# uRinks_v4_0.net
KiCad netlist of a schematic drawn in EAGLE
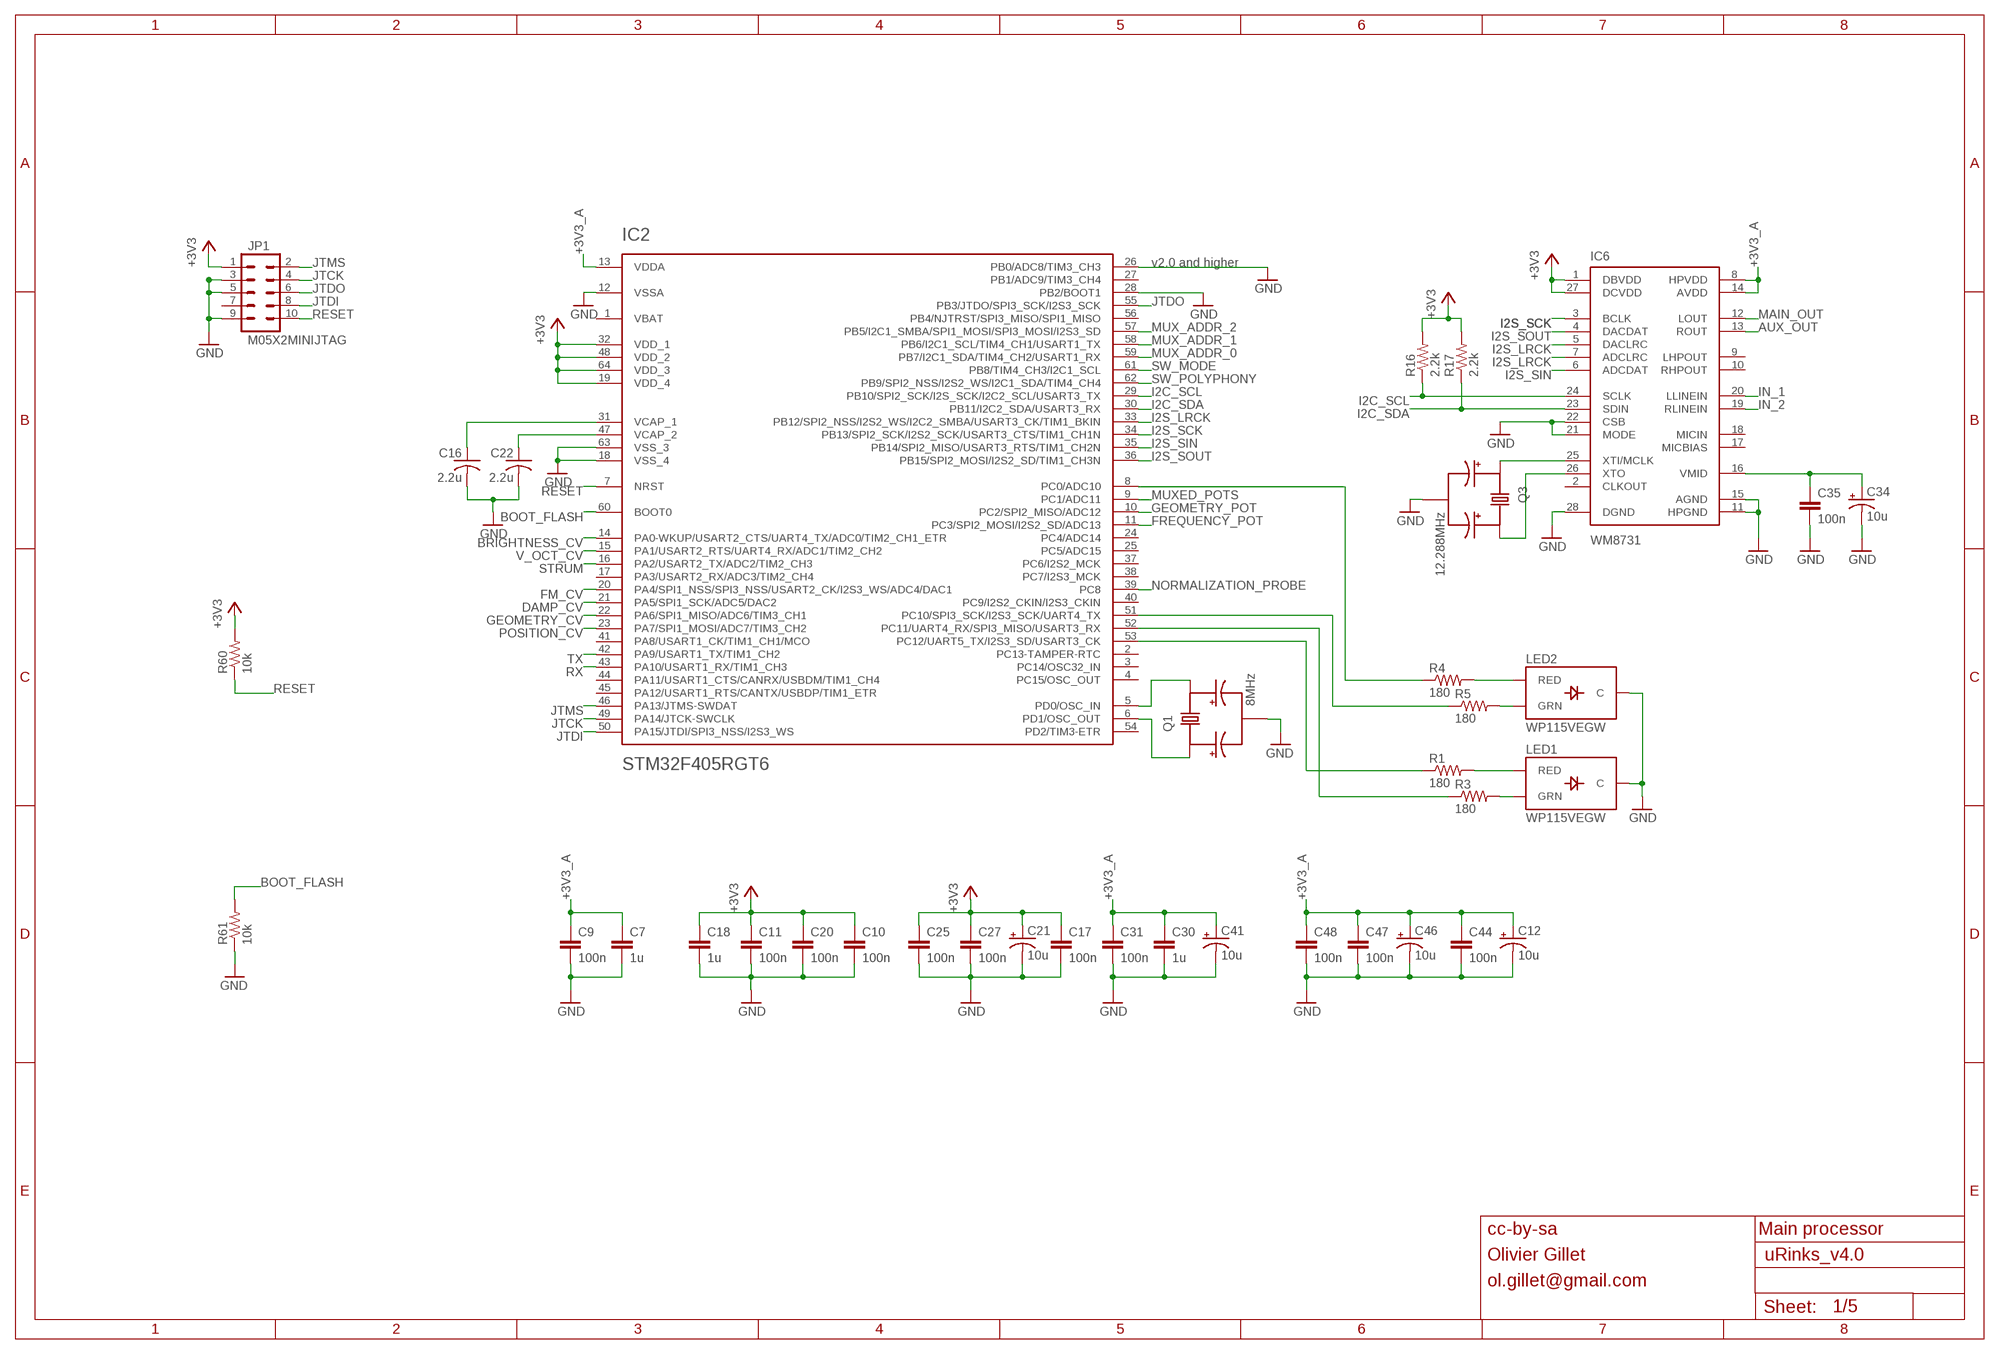
[diagram p0: schematic, sheet 1]
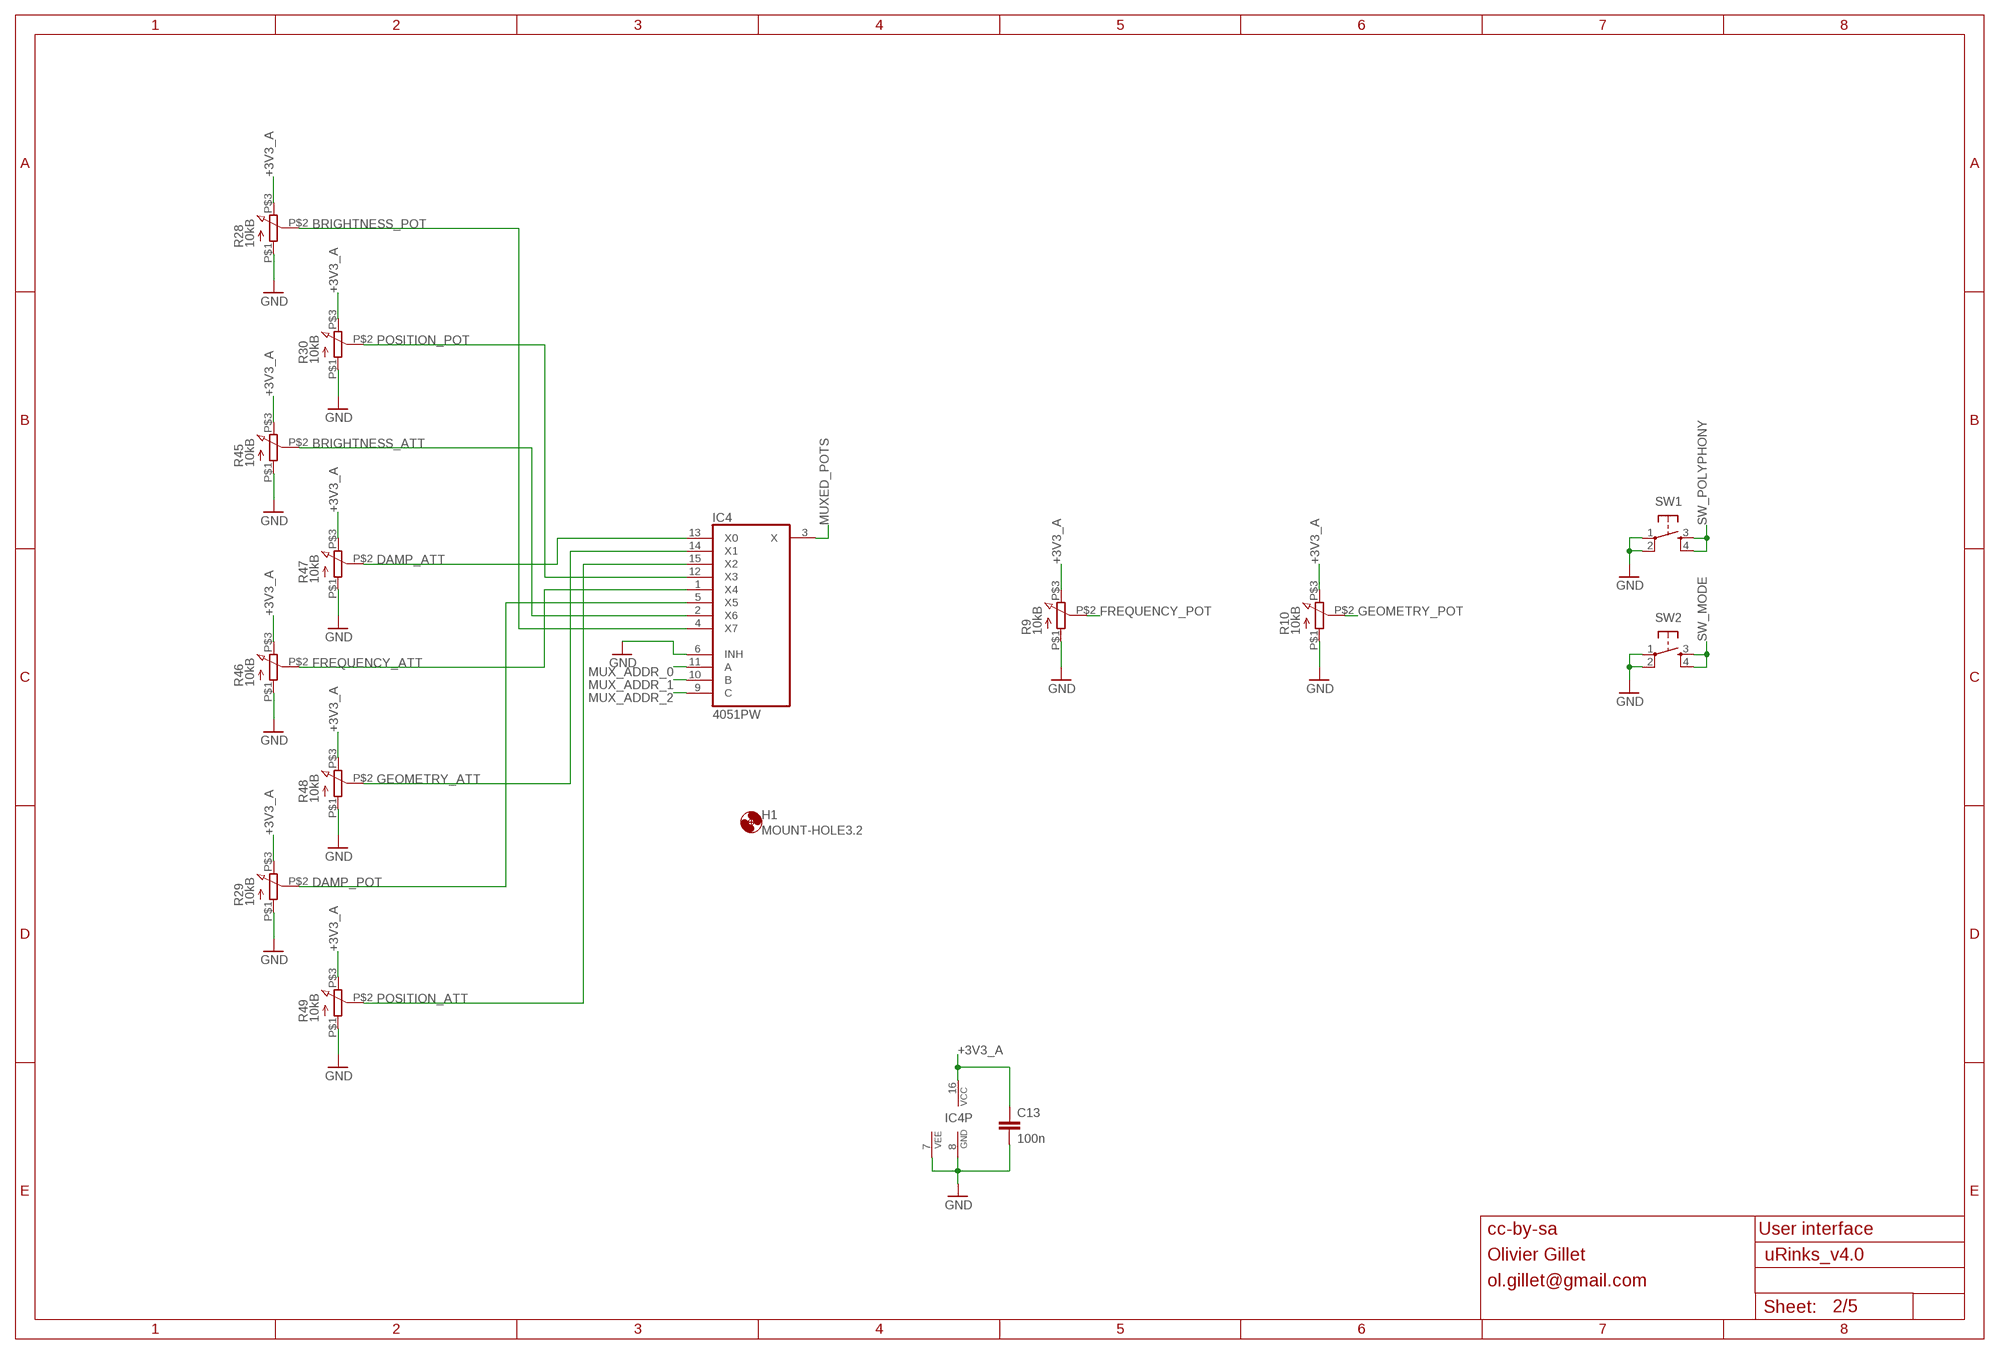
[diagram p1: schematic, sheet 2]
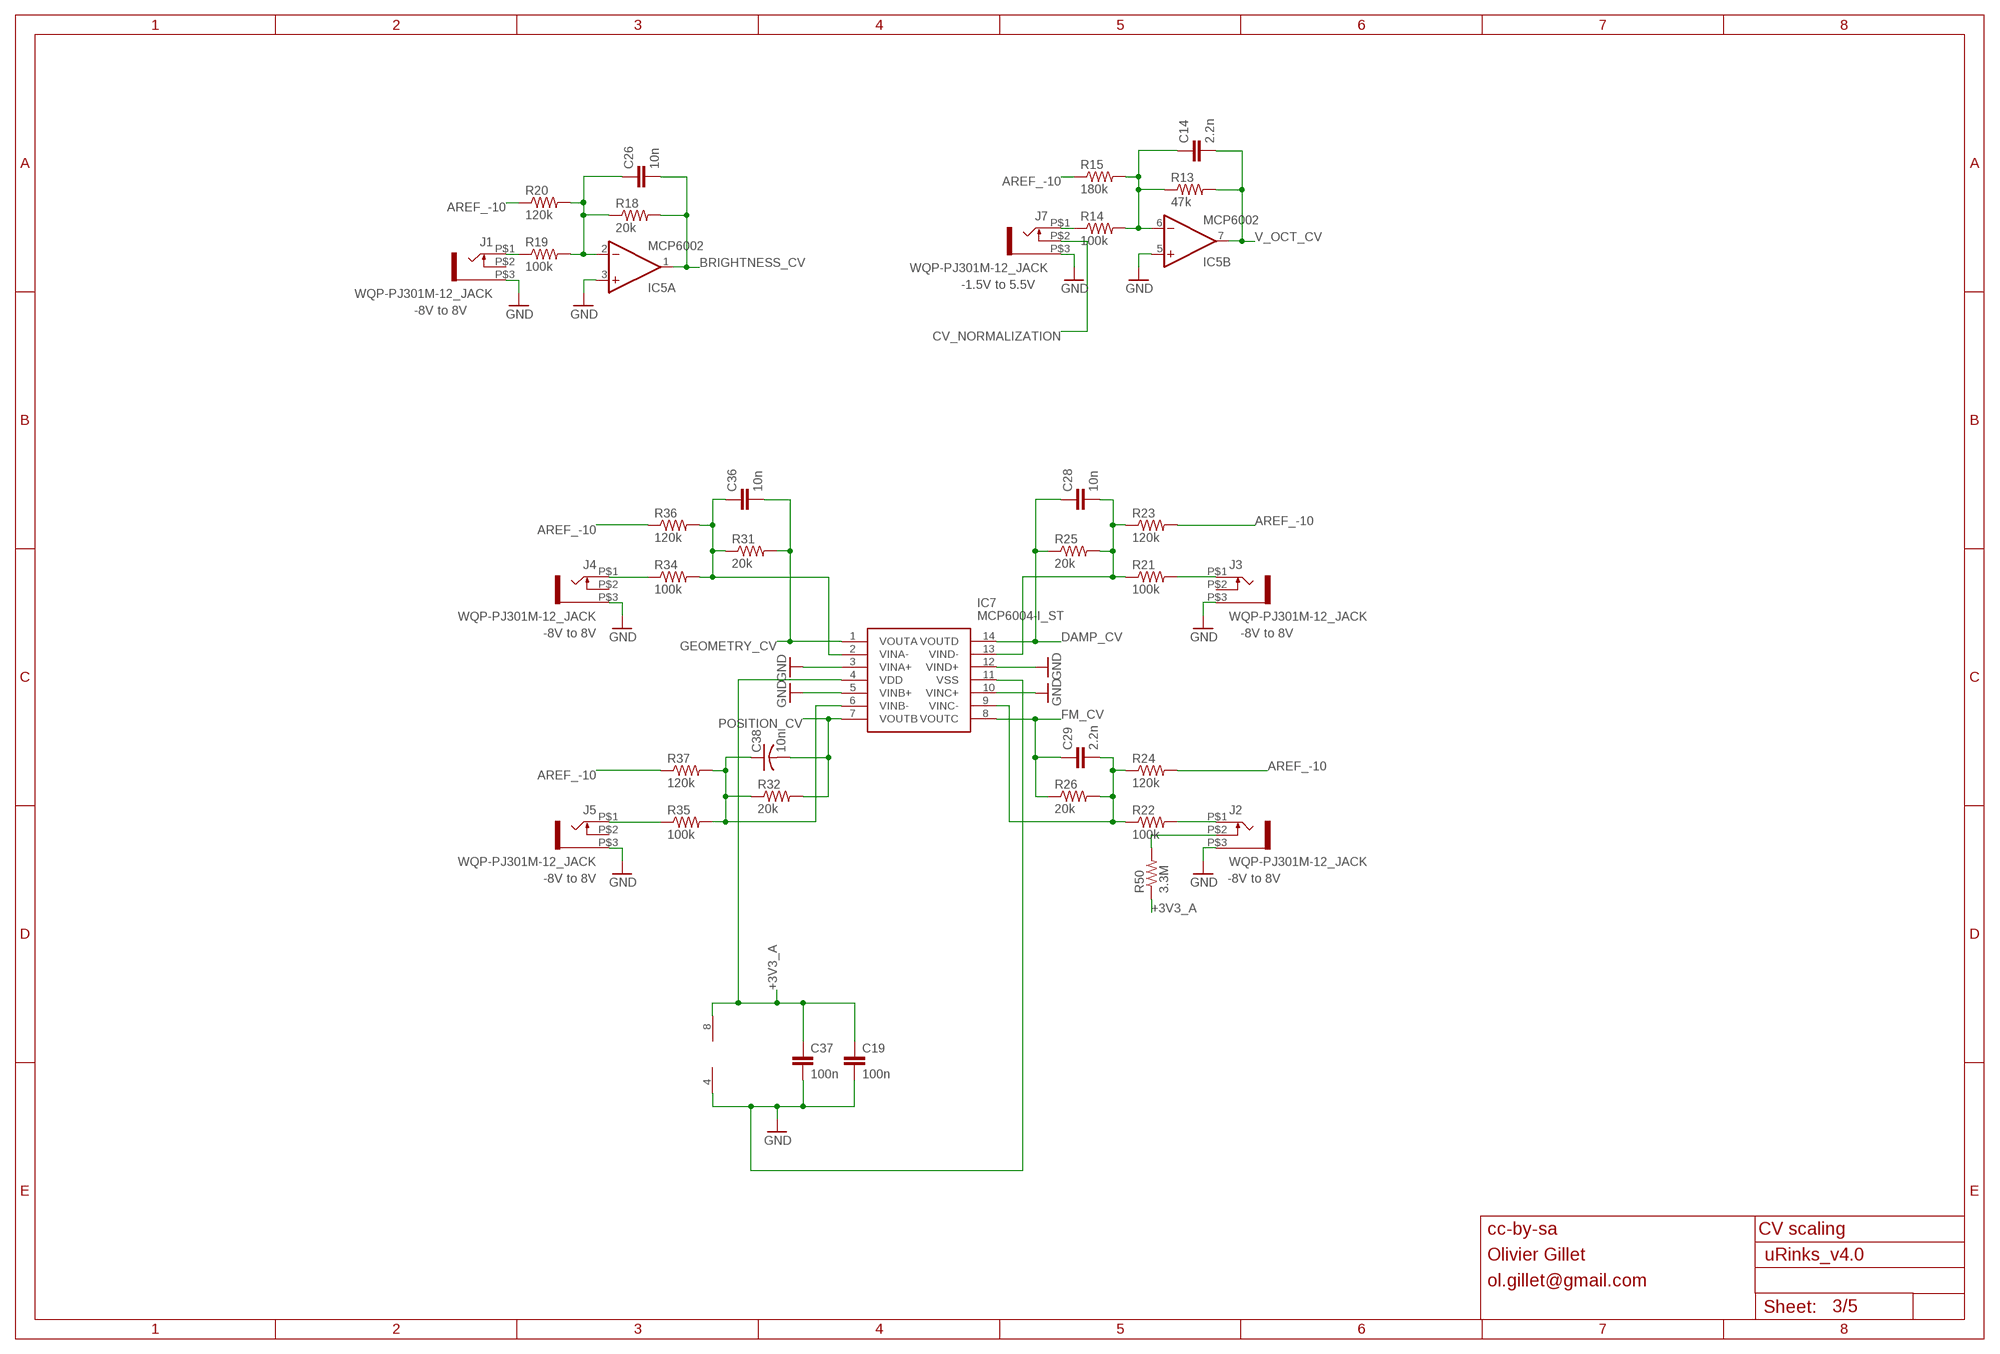
[diagram p2: schematic, sheet 3]
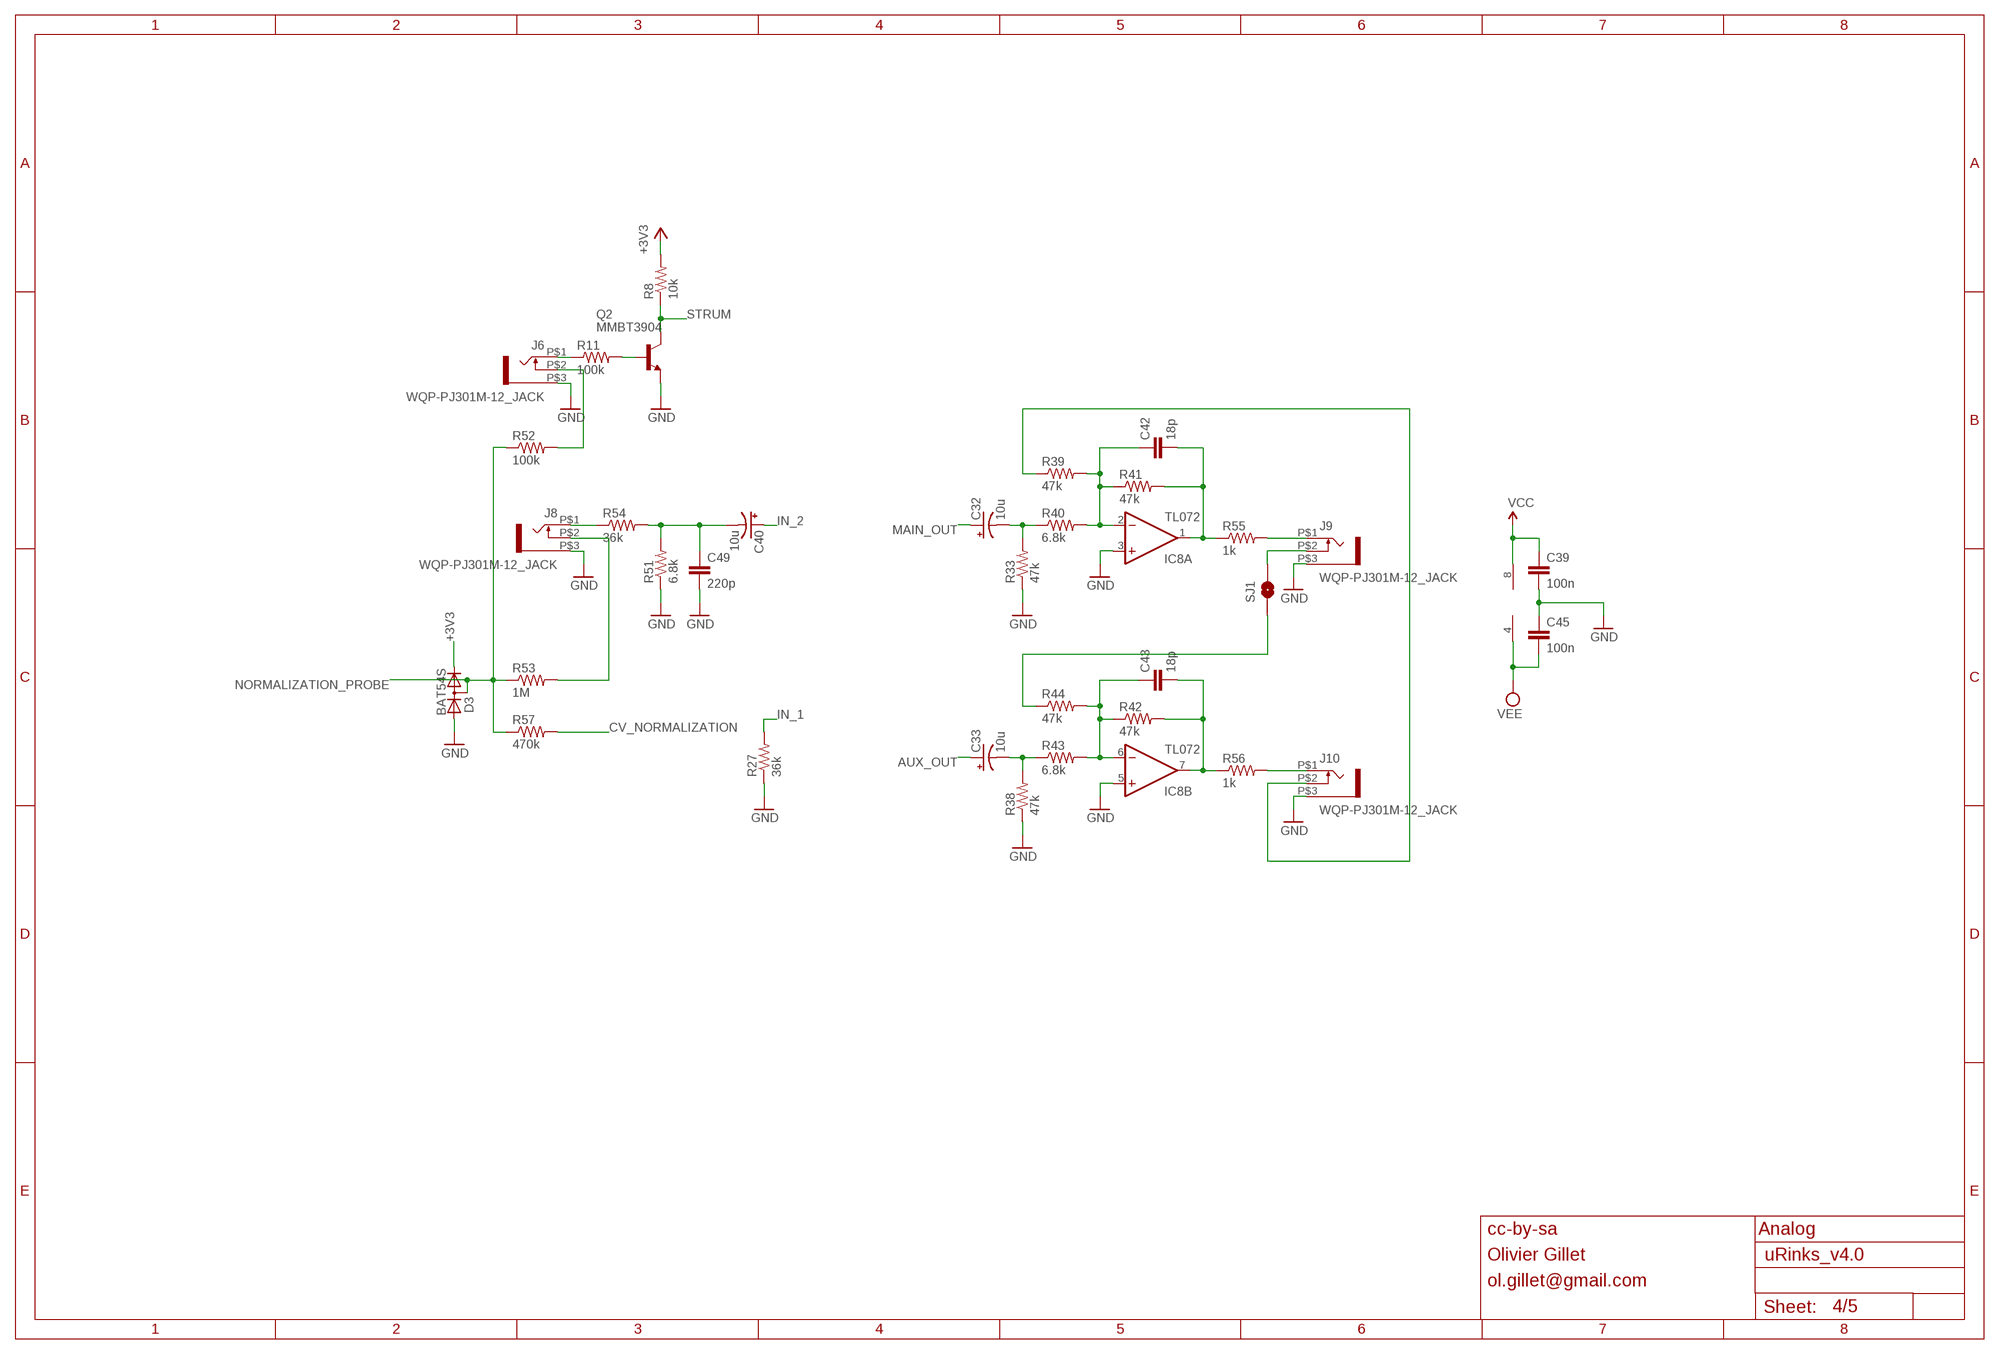
[diagram p3: schematic, sheet 4]
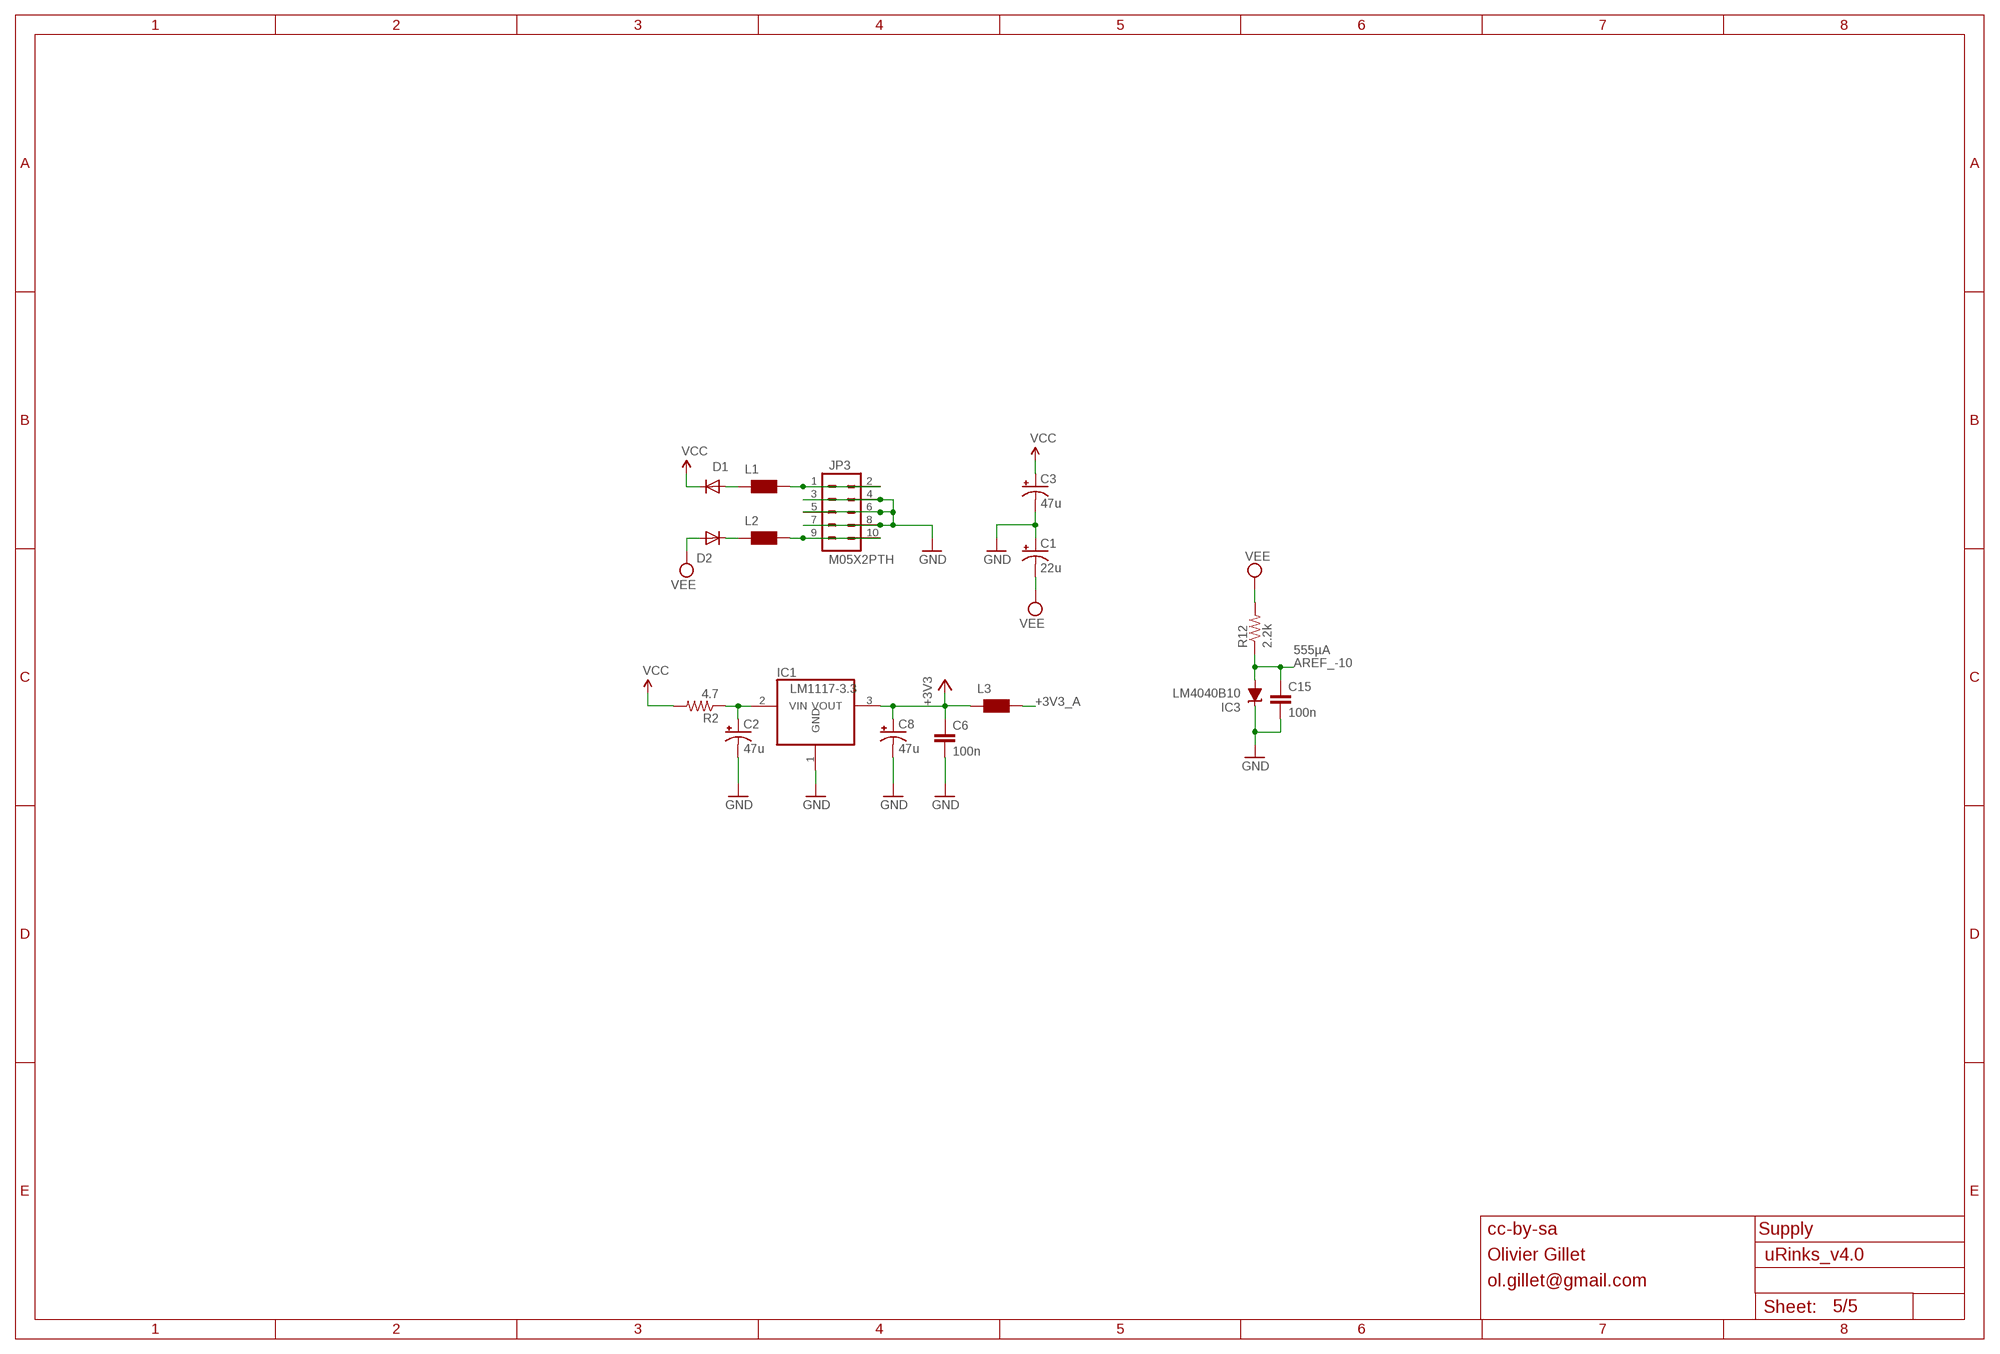
[diagram p4: schematic, sheet 5]

(export (version "E")
  (design (tool "Eeschema 10.0.6"))
  (components
    (comp (ref "C13")
      (value "100n")
      (footprint "eagle-import:PARTS_AMAN_RESISTOR_0603")
      (libsource (lib "eagle-import") (part "PARTS_AMAN_CAPACITOR"))
    )
    (comp (ref "H1")
      (value "MOUNT-HOLE3.2")
      (footprint "eagle-import:3,2")
      (libsource (lib "eagle-import") (part "MOUNT-HOLE3.2"))
    )
    (comp (ref "IC4")
      (value "4051PW")
      (footprint "eagle-import:TSSOP16")
      (libsource (lib "eagle-import") (part "4051PW"))
    )
    (comp (ref "R9")
      (value "10kB")
      (footprint "eagle-import:INSTRUO_Q-POT2")
      (libsource (lib "eagle-import") (part "INSTRUO_Q-POT2"))
    )
    (comp (ref "R10")
      (value "10kB")
      (footprint "eagle-import:INSTRUO_Q-POT2")
      (libsource (lib "eagle-import") (part "INSTRUO_Q-POT2"))
    )
    (comp (ref "R28")
      (value "10kB")
      (footprint "eagle-import:INSTRUO_Q-POT2")
      (libsource (lib "eagle-import") (part "INSTRUO_Q-POT2"))
    )
    (comp (ref "R29")
      (value "10kB")
      (footprint "eagle-import:INSTRUO_Q-POT2")
      (libsource (lib "eagle-import") (part "INSTRUO_Q-POT2"))
    )
    (comp (ref "R30")
      (value "10kB")
      (footprint "eagle-import:INSTRUO_Q-POT2")
      (libsource (lib "eagle-import") (part "INSTRUO_Q-POT2"))
    )
    (comp (ref "R45")
      (value "10kB")
      (footprint "eagle-import:INSTRUO_Q-POT2")
      (libsource (lib "eagle-import") (part "INSTRUO_Q-POT2"))
    )
    (comp (ref "R46")
      (value "10kB")
      (footprint "eagle-import:INSTRUO_Q-POT2")
      (libsource (lib "eagle-import") (part "INSTRUO_Q-POT2"))
    )
    (comp (ref "R47")
      (value "10kB")
      (footprint "eagle-import:INSTRUO_Q-POT2")
      (libsource (lib "eagle-import") (part "INSTRUO_Q-POT2"))
    )
    (comp (ref "R48")
      (value "10kB")
      (footprint "eagle-import:INSTRUO_Q-POT2")
      (libsource (lib "eagle-import") (part "INSTRUO_Q-POT2"))
    )
    (comp (ref "R49")
      (value "10kB")
      (footprint "eagle-import:INSTRUO_Q-POT2")
      (libsource (lib "eagle-import") (part "INSTRUO_Q-POT2"))
    )
    (comp (ref "SW1")
      (value "TAC_SWITCHPTH")
      (footprint "eagle-import:TACTILE-PTH")
      (libsource (lib "eagle-import") (part "TAC_SWITCHPTH"))
    )
    (comp (ref "SW2")
      (value "TAC_SWITCHPTH")
      (footprint "eagle-import:TACTILE-PTH")
      (libsource (lib "eagle-import") (part "TAC_SWITCHPTH"))
    )
    (comp (ref "C1")
      (value "22u")
      (footprint "eagle-import:PANASONIC_C")
      (libsource (lib "eagle-import") (part "CPOL-USC"))
    )
    (comp (ref "C2")
      (value "47u")
      (footprint "eagle-import:PANASONIC_D")
      (libsource (lib "eagle-import") (part "CPOL-USD"))
    )
    (comp (ref "C3")
      (value "47u")
      (footprint "eagle-import:PANASONIC_D")
      (libsource (lib "eagle-import") (part "CPOL-USD"))
    )
    (comp (ref "C6")
      (value "100n")
      (footprint "eagle-import:PARTS_AMAN_RESISTOR_0603")
      (libsource (lib "eagle-import") (part "PARTS_AMAN_CAPACITOR"))
    )
    (comp (ref "C8")
      (value "47u")
      (footprint "eagle-import:PANASONIC_D")
      (libsource (lib "eagle-import") (part "CPOL-USD"))
    )
    (comp (ref "C15")
      (value "100n")
      (footprint "eagle-import:PARTS_AMAN_RESISTOR_0603")
      (libsource (lib "eagle-import") (part "PARTS_AMAN_CAPACITOR"))
    )
    (comp (ref "D1")
      (value "1N5819HW")
      (footprint "eagle-import:SOD123")
      (libsource (lib "eagle-import") (part "DIODE-SOD123"))
    )
    (comp (ref "D2")
      (value "1N5819HW")
      (footprint "eagle-import:SOD123")
      (libsource (lib "eagle-import") (part "DIODE-SOD123"))
    )
    (comp (ref "IC1")
      (value "LM1117-3.3")
      (footprint "eagle-import:TO252")
      (libsource (lib "eagle-import") (part "REG1117T"))
    )
    (comp (ref "IC3")
      (value "LM4040B10")
      (footprint "eagle-import:DBZ_R-PDSO-G3")
      (libsource (lib "eagle-import") (part "LM4041DBZB12"))
    )
    (comp (ref "JP3")
      (value "M05X2PTH")
      (footprint "eagle-import:AVR_ICSP")
      (libsource (lib "eagle-import") (part "M05X2PTH"))
    )
    (comp (ref "L1")
      (value "WE-CBF_0603")
      (footprint "eagle-import:0603")
      (libsource (lib "eagle-import") (part "WE-CBF_0603"))
    )
    (comp (ref "L2")
      (value "WE-CBF_0603")
      (footprint "eagle-import:0603")
      (libsource (lib "eagle-import") (part "WE-CBF_0603"))
    )
    (comp (ref "L3")
      (value "WE-CBF_0603")
      (footprint "eagle-import:0603")
      (libsource (lib "eagle-import") (part "WE-CBF_0603"))
    )
    (comp (ref "R2")
      (value "4.7")
      (footprint "eagle-import:R1206")
      (libsource (lib "eagle-import") (part "R-US_R1206"))
    )
    (comp (ref "R12")
      (value "2.2k")
      (footprint "eagle-import:PARTS_AMAN_RESISTOR_0603")
      (libsource (lib "eagle-import") (part "PARTS_AMAN_RESISTOR"))
    )
    (comp (ref "C14")
      (value "2.2n")
      (footprint "eagle-import:PARTS_AMAN_RESISTOR_0603")
      (libsource (lib "eagle-import") (part "PARTS_AMAN_CAPACITOR"))
    )
    (comp (ref "C19")
      (value "100n")
      (footprint "eagle-import:PARTS_AMAN_RESISTOR_0603")
      (libsource (lib "eagle-import") (part "PARTS_AMAN_CAPACITOR"))
    )
    (comp (ref "C26")
      (value "10n")
      (footprint "eagle-import:PARTS_AMAN_RESISTOR_0603")
      (libsource (lib "eagle-import") (part "PARTS_AMAN_CAPACITOR"))
    )
    (comp (ref "C28")
      (value "10n")
      (footprint "eagle-import:PARTS_AMAN_RESISTOR_0603")
      (libsource (lib "eagle-import") (part "PARTS_AMAN_CAPACITOR"))
    )
    (comp (ref "C29")
      (value "2.2n")
      (footprint "eagle-import:PARTS_AMAN_RESISTOR_0603")
      (libsource (lib "eagle-import") (part "PARTS_AMAN_CAPACITOR"))
    )
    (comp (ref "C36")
      (value "10n")
      (footprint "eagle-import:PARTS_AMAN_RESISTOR_0603")
      (libsource (lib "eagle-import") (part "PARTS_AMAN_CAPACITOR"))
    )
    (comp (ref "C37")
      (value "100n")
      (footprint "eagle-import:PARTS_AMAN_RESISTOR_0603")
      (libsource (lib "eagle-import") (part "PARTS_AMAN_CAPACITOR"))
    )
    (comp (ref "C38")
      (value "10n")
      (footprint "eagle-import:C0603")
      (libsource (lib "eagle-import") (part "resistor_348_C-USC0603"))
    )
    (comp (ref "IC5")
      (value "MCP6002")
      (footprint "eagle-import:SO08")
      (libsource (lib "eagle-import") (part "TL072D"))
    )
    (comp (ref "IC7")
      (value "MCP6004-I_ST")
      (footprint "eagle-import:SOP65P640X120-14N")
      (fields
        (field (name "MANUFACTURER_PART_NUMBER") "MCP6004-I/ST")
        (field (name "MOUSER_PART_NUMBER") "579-MCP6004-I/ST")
      )
      (libsource (lib "eagle-import") (part "MCP6004-I_ST"))
    )
    (comp (ref "J1")
      (value "WQP-PJ301M-12_JACK")
      (footprint "eagle-import:WQP-PJ301M-12_JACK")
      (libsource (lib "eagle-import") (part "WQP-PJ301M-12_JACK"))
    )
    (comp (ref "J2")
      (value "WQP-PJ301M-12_JACK")
      (footprint "eagle-import:WQP-PJ301M-12_JACK")
      (libsource (lib "eagle-import") (part "WQP-PJ301M-12_JACK"))
    )
    (comp (ref "J3")
      (value "WQP-PJ301M-12_JACK")
      (footprint "eagle-import:WQP-PJ301M-12_JACK")
      (libsource (lib "eagle-import") (part "WQP-PJ301M-12_JACK"))
    )
    (comp (ref "J4")
      (value "WQP-PJ301M-12_JACK")
      (footprint "eagle-import:WQP-PJ301M-12_JACK")
      (libsource (lib "eagle-import") (part "WQP-PJ301M-12_JACK"))
    )
    (comp (ref "J5")
      (value "WQP-PJ301M-12_JACK")
      (footprint "eagle-import:WQP-PJ301M-12_JACK")
      (libsource (lib "eagle-import") (part "WQP-PJ301M-12_JACK"))
    )
    (comp (ref "J7")
      (value "WQP-PJ301M-12_JACK")
      (footprint "eagle-import:WQP-PJ301M-12_JACK")
      (libsource (lib "eagle-import") (part "WQP-PJ301M-12_JACK"))
    )
    (comp (ref "R13")
      (value "47k")
      (footprint "eagle-import:PARTS_AMAN_RESISTOR_0603")
      (libsource (lib "eagle-import") (part "PARTS_AMAN_RESISTOR"))
    )
    (comp (ref "R14")
      (value "100k")
      (footprint "eagle-import:PARTS_AMAN_RESISTOR_0603")
      (libsource (lib "eagle-import") (part "PARTS_AMAN_RESISTOR"))
    )
    (comp (ref "R15")
      (value "180k")
      (footprint "eagle-import:PARTS_AMAN_RESISTOR_0603")
      (libsource (lib "eagle-import") (part "PARTS_AMAN_RESISTOR"))
    )
    (comp (ref "R18")
      (value "20k")
      (footprint "eagle-import:PARTS_AMAN_RESISTOR_0603")
      (libsource (lib "eagle-import") (part "PARTS_AMAN_RESISTOR"))
    )
    (comp (ref "R19")
      (value "100k")
      (footprint "eagle-import:PARTS_AMAN_RESISTOR_0603")
      (libsource (lib "eagle-import") (part "PARTS_AMAN_RESISTOR"))
    )
    (comp (ref "R20")
      (value "120k")
      (footprint "eagle-import:PARTS_AMAN_RESISTOR_0603")
      (libsource (lib "eagle-import") (part "PARTS_AMAN_RESISTOR"))
    )
    (comp (ref "R21")
      (value "100k")
      (footprint "eagle-import:PARTS_AMAN_RESISTOR_0603")
      (libsource (lib "eagle-import") (part "PARTS_AMAN_RESISTOR"))
    )
    (comp (ref "R22")
      (value "100k")
      (footprint "eagle-import:PARTS_AMAN_RESISTOR_0603")
      (libsource (lib "eagle-import") (part "PARTS_AMAN_RESISTOR"))
    )
    (comp (ref "R23")
      (value "120k")
      (footprint "eagle-import:PARTS_AMAN_RESISTOR_0603")
      (libsource (lib "eagle-import") (part "PARTS_AMAN_RESISTOR"))
    )
    (comp (ref "R24")
      (value "120k")
      (footprint "eagle-import:PARTS_AMAN_RESISTOR_0603")
      (libsource (lib "eagle-import") (part "PARTS_AMAN_RESISTOR"))
    )
    (comp (ref "R25")
      (value "20k")
      (footprint "eagle-import:PARTS_AMAN_RESISTOR_0603")
      (libsource (lib "eagle-import") (part "PARTS_AMAN_RESISTOR"))
    )
    (comp (ref "R26")
      (value "20k")
      (footprint "eagle-import:PARTS_AMAN_RESISTOR_0603")
      (libsource (lib "eagle-import") (part "PARTS_AMAN_RESISTOR"))
    )
    (comp (ref "R31")
      (value "20k")
      (footprint "eagle-import:PARTS_AMAN_RESISTOR_0603")
      (libsource (lib "eagle-import") (part "PARTS_AMAN_RESISTOR"))
    )
    (comp (ref "R32")
      (value "20k")
      (footprint "eagle-import:PARTS_AMAN_RESISTOR_0603")
      (libsource (lib "eagle-import") (part "PARTS_AMAN_RESISTOR"))
    )
    (comp (ref "R34")
      (value "100k")
      (footprint "eagle-import:PARTS_AMAN_RESISTOR_0603")
      (libsource (lib "eagle-import") (part "PARTS_AMAN_RESISTOR"))
    )
    (comp (ref "R35")
      (value "100k")
      (footprint "eagle-import:PARTS_AMAN_RESISTOR_0603")
      (libsource (lib "eagle-import") (part "PARTS_AMAN_RESISTOR"))
    )
    (comp (ref "R36")
      (value "120k")
      (footprint "eagle-import:PARTS_AMAN_RESISTOR_0603")
      (libsource (lib "eagle-import") (part "PARTS_AMAN_RESISTOR"))
    )
    (comp (ref "R37")
      (value "120k")
      (footprint "eagle-import:PARTS_AMAN_RESISTOR_0603")
      (libsource (lib "eagle-import") (part "PARTS_AMAN_RESISTOR"))
    )
    (comp (ref "R50")
      (value "3.3M")
      (footprint "eagle-import:PARTS_AMAN_RESISTOR_0603")
      (libsource (lib "eagle-import") (part "PARTS_AMAN_RESISTOR"))
    )
    (comp (ref "C32")
      (value "10u")
      (footprint "eagle-import:PANASONIC_A")
      (libsource (lib "eagle-import") (part "CPOL-USA"))
    )
    (comp (ref "C33")
      (value "10u")
      (footprint "eagle-import:PANASONIC_A")
      (libsource (lib "eagle-import") (part "CPOL-USA"))
    )
    (comp (ref "C39")
      (value "100n")
      (footprint "eagle-import:PARTS_AMAN_RESISTOR_0603")
      (libsource (lib "eagle-import") (part "PARTS_AMAN_CAPACITOR"))
    )
    (comp (ref "C40")
      (value "10u")
      (footprint "eagle-import:PANASONIC_A")
      (libsource (lib "eagle-import") (part "CPOL-USA"))
    )
    (comp (ref "C42")
      (value "18p")
      (footprint "eagle-import:PARTS_AMAN_RESISTOR_0603")
      (libsource (lib "eagle-import") (part "PARTS_AMAN_CAPACITOR"))
    )
    (comp (ref "C43")
      (value "18p")
      (footprint "eagle-import:PARTS_AMAN_RESISTOR_0603")
      (libsource (lib "eagle-import") (part "PARTS_AMAN_CAPACITOR"))
    )
    (comp (ref "C45")
      (value "100n")
      (footprint "eagle-import:PARTS_AMAN_RESISTOR_0603")
      (libsource (lib "eagle-import") (part "PARTS_AMAN_CAPACITOR"))
    )
    (comp (ref "C49")
      (value "220p")
      (footprint "eagle-import:PARTS_AMAN_RESISTOR_0603")
      (libsource (lib "eagle-import") (part "PARTS_AMAN_CAPACITOR"))
    )
    (comp (ref "D3")
      (value "BAT54S")
      (footprint "eagle-import:SOT23")
      (libsource (lib "eagle-import") (part "DIODE_2CACA-SOT23"))
    )
    (comp (ref "IC8")
      (value "TL072")
      (footprint "eagle-import:SO08")
      (libsource (lib "eagle-import") (part "og-linear_TL072D"))
    )
    (comp (ref "J6")
      (value "WQP-PJ301M-12_JACK")
      (footprint "eagle-import:WQP-PJ301M-12_JACK")
      (libsource (lib "eagle-import") (part "WQP-PJ301M-12_JACK"))
    )
    (comp (ref "J8")
      (value "WQP-PJ301M-12_JACK")
      (footprint "eagle-import:WQP-PJ301M-12_JACK")
      (libsource (lib "eagle-import") (part "WQP-PJ301M-12_JACK"))
    )
    (comp (ref "J9")
      (value "WQP-PJ301M-12_JACK")
      (footprint "eagle-import:WQP-PJ301M-12_JACK")
      (libsource (lib "eagle-import") (part "WQP-PJ301M-12_JACK"))
    )
    (comp (ref "J10")
      (value "WQP-PJ301M-12_JACK")
      (footprint "eagle-import:WQP-PJ301M-12_JACK")
      (libsource (lib "eagle-import") (part "WQP-PJ301M-12_JACK"))
    )
    (comp (ref "Q2")
      (value "MMBT3904")
      (footprint "eagle-import:SOT23-BEC")
      (libsource (lib "eagle-import") (part "-NPN-SOT23-BECMMBT3904LT1"))
    )
    (comp (ref "R8")
      (value "10k")
      (footprint "eagle-import:PARTS_AMAN_RESISTOR_0603")
      (libsource (lib "eagle-import") (part "PARTS_AMAN_RESISTOR"))
    )
    (comp (ref "R11")
      (value "100k")
      (footprint "eagle-import:PARTS_AMAN_RESISTOR_0603")
      (libsource (lib "eagle-import") (part "PARTS_AMAN_RESISTOR"))
    )
    (comp (ref "R27")
      (value "36k")
      (footprint "eagle-import:PARTS_AMAN_RESISTOR_0603")
      (libsource (lib "eagle-import") (part "PARTS_AMAN_RESISTOR"))
    )
    (comp (ref "R33")
      (value "47k")
      (footprint "eagle-import:PARTS_AMAN_RESISTOR_0603")
      (libsource (lib "eagle-import") (part "PARTS_AMAN_RESISTOR"))
    )
    (comp (ref "R38")
      (value "47k")
      (footprint "eagle-import:PARTS_AMAN_RESISTOR_0603")
      (libsource (lib "eagle-import") (part "PARTS_AMAN_RESISTOR"))
    )
    (comp (ref "R39")
      (value "47k")
      (footprint "eagle-import:PARTS_AMAN_RESISTOR_0603")
      (libsource (lib "eagle-import") (part "PARTS_AMAN_RESISTOR"))
    )
    (comp (ref "R40")
      (value "6.8k")
      (footprint "eagle-import:PARTS_AMAN_RESISTOR_0603")
      (libsource (lib "eagle-import") (part "PARTS_AMAN_RESISTOR"))
    )
    (comp (ref "R41")
      (value "47k")
      (footprint "eagle-import:PARTS_AMAN_RESISTOR_0603")
      (libsource (lib "eagle-import") (part "PARTS_AMAN_RESISTOR"))
    )
    (comp (ref "R42")
      (value "47k")
      (footprint "eagle-import:PARTS_AMAN_RESISTOR_0603")
      (libsource (lib "eagle-import") (part "PARTS_AMAN_RESISTOR"))
    )
    (comp (ref "R43")
      (value "6.8k")
      (footprint "eagle-import:PARTS_AMAN_RESISTOR_0603")
      (libsource (lib "eagle-import") (part "PARTS_AMAN_RESISTOR"))
    )
    (comp (ref "R44")
      (value "47k")
      (footprint "eagle-import:PARTS_AMAN_RESISTOR_0603")
      (libsource (lib "eagle-import") (part "PARTS_AMAN_RESISTOR"))
    )
    (comp (ref "R51")
      (value "6.8k")
      (footprint "eagle-import:PARTS_AMAN_RESISTOR_0603")
      (libsource (lib "eagle-import") (part "PARTS_AMAN_RESISTOR"))
    )
    (comp (ref "R52")
      (value "100k")
      (footprint "eagle-import:R0603")
      (libsource (lib "eagle-import") (part "R-US_R0603"))
    )
    (comp (ref "R53")
      (value "1M")
      (footprint "eagle-import:PARTS_AMAN_RESISTOR_0603")
      (libsource (lib "eagle-import") (part "PARTS_AMAN_RESISTOR"))
    )
    (comp (ref "R54")
      (value "36k")
      (footprint "eagle-import:PARTS_AMAN_RESISTOR_0603")
      (libsource (lib "eagle-import") (part "PARTS_AMAN_RESISTOR"))
    )
    (comp (ref "R55")
      (value "1k")
      (footprint "eagle-import:PARTS_AMAN_RESISTOR_0603")
      (libsource (lib "eagle-import") (part "PARTS_AMAN_RESISTOR"))
    )
    (comp (ref "R56")
      (value "1k")
      (footprint "eagle-import:PARTS_AMAN_RESISTOR_0603")
      (libsource (lib "eagle-import") (part "PARTS_AMAN_RESISTOR"))
    )
    (comp (ref "R57")
      (value "470k")
      (footprint "eagle-import:PARTS_AMAN_RESISTOR_0603")
      (libsource (lib "eagle-import") (part "PARTS_AMAN_RESISTOR"))
    )
    (comp (ref "SJ1")
      (value "SOLDERJUMPERNC2")
      (footprint "eagle-import:SJ_2S-NOTRACE")
      (libsource (lib "eagle-import") (part "SOLDERJUMPERNC2"))
    )
    (comp (ref "C7")
      (value "1u")
      (footprint "eagle-import:PARTS_AMAN_RESISTOR_0603")
      (libsource (lib "eagle-import") (part "PARTS_AMAN_CAPACITOR"))
    )
    (comp (ref "C9")
      (value "100n")
      (footprint "eagle-import:PARTS_AMAN_RESISTOR_0603")
      (libsource (lib "eagle-import") (part "PARTS_AMAN_CAPACITOR"))
    )
    (comp (ref "C10")
      (value "100n")
      (footprint "eagle-import:PARTS_AMAN_RESISTOR_0603")
      (libsource (lib "eagle-import") (part "PARTS_AMAN_CAPACITOR"))
    )
    (comp (ref "C11")
      (value "100n")
      (footprint "eagle-import:PARTS_AMAN_RESISTOR_0603")
      (libsource (lib "eagle-import") (part "PARTS_AMAN_CAPACITOR"))
    )
    (comp (ref "C12")
      (value "10u")
      (footprint "eagle-import:PANASONIC_A")
      (libsource (lib "eagle-import") (part "CPOL-USA"))
    )
    (comp (ref "C16")
      (value "2.2u")
      (footprint "eagle-import:C0805")
      (libsource (lib "eagle-import") (part "C-USC0805"))
    )
    (comp (ref "C17")
      (value "100n")
      (footprint "eagle-import:PARTS_AMAN_RESISTOR_0603")
      (libsource (lib "eagle-import") (part "PARTS_AMAN_CAPACITOR"))
    )
    (comp (ref "C18")
      (value "1u")
      (footprint "eagle-import:PARTS_AMAN_RESISTOR_0603")
      (libsource (lib "eagle-import") (part "PARTS_AMAN_CAPACITOR"))
    )
    (comp (ref "C20")
      (value "100n")
      (footprint "eagle-import:PARTS_AMAN_RESISTOR_0603")
      (libsource (lib "eagle-import") (part "PARTS_AMAN_CAPACITOR"))
    )
    (comp (ref "C21")
      (value "10u")
      (footprint "eagle-import:PANASONIC_A")
      (libsource (lib "eagle-import") (part "CPOL-USA"))
    )
    (comp (ref "C22")
      (value "2.2u")
      (footprint "eagle-import:C0805")
      (libsource (lib "eagle-import") (part "C-USC0805"))
    )
    (comp (ref "C25")
      (value "100n")
      (footprint "eagle-import:PARTS_AMAN_RESISTOR_0603")
      (libsource (lib "eagle-import") (part "PARTS_AMAN_CAPACITOR"))
    )
    (comp (ref "C27")
      (value "100n")
      (footprint "eagle-import:PARTS_AMAN_RESISTOR_0603")
      (libsource (lib "eagle-import") (part "PARTS_AMAN_CAPACITOR"))
    )
    (comp (ref "C30")
      (value "1u")
      (footprint "eagle-import:PARTS_AMAN_RESISTOR_0603")
      (libsource (lib "eagle-import") (part "PARTS_AMAN_CAPACITOR"))
    )
    (comp (ref "C31")
      (value "100n")
      (footprint "eagle-import:PARTS_AMAN_RESISTOR_0603")
      (libsource (lib "eagle-import") (part "PARTS_AMAN_CAPACITOR"))
    )
    (comp (ref "C34")
      (value "10u")
      (footprint "eagle-import:PANASONIC_A")
      (libsource (lib "eagle-import") (part "CPOL-USA"))
    )
    (comp (ref "C35")
      (value "100n")
      (footprint "eagle-import:PARTS_AMAN_RESISTOR_0603")
      (libsource (lib "eagle-import") (part "PARTS_AMAN_CAPACITOR"))
    )
    (comp (ref "C41")
      (value "10u")
      (footprint "eagle-import:PANASONIC_A")
      (libsource (lib "eagle-import") (part "CPOL-USA"))
    )
    (comp (ref "C44")
      (value "100n")
      (footprint "eagle-import:PARTS_AMAN_RESISTOR_0603")
      (libsource (lib "eagle-import") (part "PARTS_AMAN_CAPACITOR"))
    )
    (comp (ref "C46")
      (value "10u")
      (footprint "eagle-import:PANASONIC_A")
      (libsource (lib "eagle-import") (part "CPOL-USA"))
    )
    (comp (ref "C47")
      (value "100n")
      (footprint "eagle-import:PARTS_AMAN_RESISTOR_0603")
      (libsource (lib "eagle-import") (part "PARTS_AMAN_CAPACITOR"))
    )
    (comp (ref "C48")
      (value "100n")
      (footprint "eagle-import:PARTS_AMAN_RESISTOR_0603")
      (libsource (lib "eagle-import") (part "PARTS_AMAN_CAPACITOR"))
    )
    (comp (ref "IC2")
      (value "STM32F405RGT6")
      (footprint "eagle-import:TQFP-10X10-64")
      (libsource (lib "eagle-import") (part "STM32F20X"))
    )
    (comp (ref "IC6")
      (value "WM8731")
      (footprint "eagle-import:SSOP28")
      (libsource (lib "eagle-import") (part "WM8731"))
    )
    (comp (ref "JP1")
      (value "M05X2MINIJTAG")
      (footprint "eagle-import:2X5-1.27")
      (libsource (lib "eagle-import") (part "M05X2MINIJTAG"))
    )
    (comp (ref "LED1")
      (value "WP115VEGW")
      (footprint "eagle-import:LED-BICOLOR-THROUGHHOLE")
      (libsource (lib "eagle-import") (part "LED-BICOLOR-THROUGHHOLE"))
    )
    (comp (ref "LED2")
      (value "WP115VEGW")
      (footprint "eagle-import:LED-BICOLOR-THROUGHHOLE")
      (libsource (lib "eagle-import") (part "LED-BICOLOR-THROUGHHOLE"))
    )
    (comp (ref "Q1")
      (value "8MHz")
      (footprint "eagle-import:INSTRUO_CRYSTAL_SMALLER")
      (libsource (lib "eagle-import") (part "INSTRUO_CRYSTAL_SMALLER"))
    )
    (comp (ref "Q3")
      (value "12.288MHz")
      (footprint "eagle-import:INSTRUO_CRYSTAL_SMALLER")
      (libsource (lib "eagle-import") (part "INSTRUO_CRYSTAL_SMALLER"))
    )
    (comp (ref "R1")
      (value "180")
      (footprint "eagle-import:PARTS_AMAN_RESISTOR_0603")
      (libsource (lib "eagle-import") (part "PARTS_AMAN_RESISTOR"))
    )
    (comp (ref "R3")
      (value "180")
      (footprint "eagle-import:PARTS_AMAN_RESISTOR_0603")
      (libsource (lib "eagle-import") (part "PARTS_AMAN_RESISTOR"))
    )
    (comp (ref "R4")
      (value "180")
      (footprint "eagle-import:PARTS_AMAN_RESISTOR_0603")
      (libsource (lib "eagle-import") (part "PARTS_AMAN_RESISTOR"))
    )
    (comp (ref "R5")
      (value "180")
      (footprint "eagle-import:PARTS_AMAN_RESISTOR_0603")
      (libsource (lib "eagle-import") (part "PARTS_AMAN_RESISTOR"))
    )
    (comp (ref "R16")
      (value "2.2k")
      (footprint "eagle-import:PARTS_AMAN_RESISTOR_0603")
      (libsource (lib "eagle-import") (part "PARTS_AMAN_RESISTOR"))
    )
    (comp (ref "R17")
      (value "2.2k")
      (footprint "eagle-import:PARTS_AMAN_RESISTOR_0603")
      (libsource (lib "eagle-import") (part "PARTS_AMAN_RESISTOR"))
    )
    (comp (ref "R60")
      (value "10k")
      (footprint "eagle-import:PARTS_AMAN_RESISTOR_0603")
      (libsource (lib "eagle-import") (part "PARTS_AMAN_RESISTOR"))
    )
    (comp (ref "R61")
      (value "10k")
      (footprint "eagle-import:PARTS_AMAN_RESISTOR_0603")
      (libsource (lib "eagle-import") (part "PARTS_AMAN_RESISTOR"))
    )
  )
  (nets
    (net (code "1") (name "+3V3") (class "Default")
      (node (ref "C10") (pin "1") (pinfunction "1_1") (pintype "passive"))
      (node (ref "C11") (pin "1") (pinfunction "1_1") (pintype "passive"))
      (node (ref "C17") (pin "1") (pinfunction "1_1") (pintype "passive"))
      (node (ref "C18") (pin "1") (pinfunction "1_1") (pintype "passive"))
      (node (ref "C20") (pin "1") (pinfunction "1_1") (pintype "passive"))
      (node (ref "C21") (pin "+") (pinfunction "+_+") (pintype "passive"))
      (node (ref "C25") (pin "1") (pinfunction "1_1") (pintype "passive"))
      (node (ref "C27") (pin "1") (pinfunction "1_1") (pintype "passive"))
      (node (ref "C6") (pin "1") (pinfunction "1_1") (pintype "passive"))
      (node (ref "C8") (pin "+") (pinfunction "+_+") (pintype "passive"))
      (node (ref "D3") (pin "2") (pinfunction "C_2") (pintype "passive"))
      (node (ref "IC1") (pin "3") (pinfunction "VOUT_3") (pintype "output"))
      (node (ref "IC2") (pin "19") (pinfunction "VDD_4_19") (pintype "power_in"))
      (node (ref "IC2") (pin "32") (pinfunction "VDD_1_32") (pintype "power_in"))
      (node (ref "IC2") (pin "48") (pinfunction "VDD_2_48") (pintype "power_in"))
      (node (ref "IC2") (pin "64") (pinfunction "VDD_3_64") (pintype "power_in"))
      (node (ref "IC6") (pin "1") (pinfunction "DBVDD_1") (pintype "bidirectional"))
      (node (ref "IC6") (pin "27") (pinfunction "DCVDD_27") (pintype "bidirectional"))
      (node (ref "JP1") (pin "1") (pinfunction "1_1") (pintype "passive"))
      (node (ref "L3") (pin "1") (pinfunction "1_1") (pintype "passive"))
      (node (ref "R16") (pin "2") (pinfunction "2_2") (pintype "passive"))
      (node (ref "R17") (pin "2") (pinfunction "2_2") (pintype "passive"))
      (node (ref "R60") (pin "2") (pinfunction "2_2") (pintype "passive"))
      (node (ref "R8") (pin "2") (pinfunction "2_2") (pintype "passive"))
    )
    (net (code "2") (name "+3V3_A") (class "Default")
      (node (ref "C12") (pin "+") (pinfunction "+_+") (pintype "passive"))
      (node (ref "C13") (pin "1") (pinfunction "1_1") (pintype "passive"))
      (node (ref "C19") (pin "1") (pinfunction "1_1") (pintype "passive"))
      (node (ref "C30") (pin "1") (pinfunction "1_1") (pintype "passive"))
      (node (ref "C31") (pin "1") (pinfunction "1_1") (pintype "passive"))
      (node (ref "C37") (pin "1") (pinfunction "1_1") (pintype "passive"))
      (node (ref "C41") (pin "+") (pinfunction "+_+") (pintype "passive"))
      (node (ref "C44") (pin "1") (pinfunction "1_1") (pintype "passive"))
      (node (ref "C46") (pin "+") (pinfunction "+_+") (pintype "passive"))
      (node (ref "C47") (pin "1") (pinfunction "1_1") (pintype "passive"))
      (node (ref "C48") (pin "1") (pinfunction "1_1") (pintype "passive"))
      (node (ref "C7") (pin "1") (pinfunction "1_1") (pintype "passive"))
      (node (ref "C9") (pin "1") (pinfunction "1_1") (pintype "passive"))
      (node (ref "IC2") (pin "13") (pinfunction "VDDA_13") (pintype "power_in"))
      (node (ref "IC4") (pin "16") (pinfunction "VCC_16") (pintype "power_in"))
      (node (ref "IC5") (pin "8") (pinfunction "V+_8") (pintype "power_in"))
      (node (ref "IC6") (pin "14") (pinfunction "AVDD_14") (pintype "bidirectional"))
      (node (ref "IC6") (pin "8") (pinfunction "HPVDD_8") (pintype "bidirectional"))
      (node (ref "IC7") (pin "4") (pinfunction "VDD_4") (pintype "power_in"))
      (node (ref "L3") (pin "2") (pinfunction "2_2") (pintype "passive"))
      (node (ref "R10") (pin "P$3") (pinfunction "3_P$3") (pintype "passive"))
      (node (ref "R28") (pin "P$3") (pinfunction "3_P$3") (pintype "passive"))
      (node (ref "R29") (pin "P$3") (pinfunction "3_P$3") (pintype "passive"))
      (node (ref "R30") (pin "P$3") (pinfunction "3_P$3") (pintype "passive"))
      (node (ref "R45") (pin "P$3") (pinfunction "3_P$3") (pintype "passive"))
      (node (ref "R46") (pin "P$3") (pinfunction "3_P$3") (pintype "passive"))
      (node (ref "R47") (pin "P$3") (pinfunction "3_P$3") (pintype "passive"))
      (node (ref "R48") (pin "P$3") (pinfunction "3_P$3") (pintype "passive"))
      (node (ref "R49") (pin "P$3") (pinfunction "3_P$3") (pintype "passive"))
      (node (ref "R50") (pin "1") (pinfunction "1_1") (pintype "passive"))
      (node (ref "R9") (pin "P$3") (pinfunction "3_P$3") (pintype "passive"))
    )
    (net (code "3") (name "AREF_-10") (class "Default")
      (node (ref "C15") (pin "1") (pinfunction "1_1") (pintype "passive"))
      (node (ref "IC3") (pin "2") (pinfunction "A_2") (pintype "passive"))
      (node (ref "R12") (pin "1") (pinfunction "1_1") (pintype "passive"))
      (node (ref "R15") (pin "1") (pinfunction "1_1") (pintype "passive"))
      (node (ref "R20") (pin "1") (pinfunction "1_1") (pintype "passive"))
      (node (ref "R23") (pin "2") (pinfunction "2_2") (pintype "passive"))
      (node (ref "R24") (pin "2") (pinfunction "2_2") (pintype "passive"))
      (node (ref "R36") (pin "1") (pinfunction "1_1") (pintype "passive"))
      (node (ref "R37") (pin "1") (pinfunction "1_1") (pintype "passive"))
    )
    (net (code "4") (name "AUX_OUT") (class "Default")
      (node (ref "C33") (pin "+") (pinfunction "+_+") (pintype "passive"))
      (node (ref "IC6") (pin "13") (pinfunction "ROUT_13") (pintype "bidirectional"))
    )
    (net (code "5") (name "BOOT_FLASH") (class "Default")
      (node (ref "IC2") (pin "60") (pinfunction "BOOT0_60") (pintype "bidirectional"))
      (node (ref "R61") (pin "2") (pinfunction "2_2") (pintype "passive"))
    )
    (net (code "6") (name "BRIGHTNESS_ATT") (class "Default")
      (node (ref "IC4") (pin "2") (pinfunction "X6_2") (pintype "bidirectional"))
      (node (ref "R45") (pin "P$2") (pinfunction "2_P$2") (pintype "passive"))
    )
    (net (code "7") (name "BRIGHTNESS_CV") (class "Default")
      (node (ref "C26") (pin "2") (pinfunction "2_2") (pintype "passive"))
      (node (ref "IC2") (pin "14") (pinfunction "PA0-WKUP/USART2_CTS/UART4_TX/ADC0/TIM2_CH1_ETR_14") (pintype "bidirectional"))
      (node (ref "IC5") (pin "1") (pinfunction "OUT_1") (pintype "output"))
      (node (ref "R18") (pin "2") (pinfunction "2_2") (pintype "passive"))
    )
    (net (code "8") (name "BRIGHTNESS_POT") (class "Default")
      (node (ref "IC4") (pin "4") (pinfunction "X7_4") (pintype "bidirectional"))
      (node (ref "R28") (pin "P$2") (pinfunction "2_P$2") (pintype "passive"))
    )
    (net (code "9") (name "CV_NORMALIZATION") (class "Default")
      (node (ref "J7") (pin "P$2") (pinfunction "3_P$2") (pintype "passive"))
      (node (ref "R57") (pin "2") (pinfunction "2_2") (pintype "passive"))
    )
    (net (code "10") (name "DAMP_ATT") (class "Default")
      (node (ref "IC4") (pin "13") (pinfunction "X0_13") (pintype "bidirectional"))
      (node (ref "R47") (pin "P$2") (pinfunction "2_P$2") (pintype "passive"))
    )
    (net (code "11") (name "DAMP_CV") (class "Default")
      (node (ref "C28") (pin "1") (pinfunction "1_1") (pintype "passive"))
      (node (ref "IC2") (pin "21") (pinfunction "PA5/SPI1_SCK/ADC5/DAC2_21") (pintype "bidirectional"))
      (node (ref "IC7") (pin "14") (pinfunction "VOUTD_14") (pintype "output"))
      (node (ref "R25") (pin "1") (pinfunction "1_1") (pintype "passive"))
    )
    (net (code "12") (name "DAMP_POT") (class "Default")
      (node (ref "IC4") (pin "5") (pinfunction "X5_5") (pintype "bidirectional"))
      (node (ref "R29") (pin "P$2") (pinfunction "2_P$2") (pintype "passive"))
    )
    (net (code "13") (name "FM_CV") (class "Default")
      (node (ref "C29") (pin "1") (pinfunction "1_1") (pintype "passive"))
      (node (ref "IC2") (pin "20") (pinfunction "PA4/SPI1_NSS/SPI3_NSS/USART2_CK/I2S3_WS/ADC4/DAC1_20") (pintype "bidirectional"))
      (node (ref "IC7") (pin "8") (pinfunction "VOUTC_8") (pintype "output"))
      (node (ref "R26") (pin "1") (pinfunction "1_1") (pintype "passive"))
    )
    (net (code "14") (name "FREQUENCY_ATT") (class "Default")
      (node (ref "IC4") (pin "1") (pinfunction "X4_1") (pintype "bidirectional"))
      (node (ref "R46") (pin "P$2") (pinfunction "2_P$2") (pintype "passive"))
    )
    (net (code "15") (name "FREQUENCY_POT") (class "Default")
      (node (ref "IC2") (pin "11") (pinfunction "PC3/SPI2_MOSI/I2S2_SD/ADC13_11") (pintype "bidirectional"))
      (node (ref "R9") (pin "P$2") (pinfunction "2_P$2") (pintype "passive"))
    )
    (net (code "16") (name "GEOMETRY_ATT") (class "Default")
      (node (ref "IC4") (pin "14") (pinfunction "X1_14") (pintype "bidirectional"))
      (node (ref "R48") (pin "P$2") (pinfunction "2_P$2") (pintype "passive"))
    )
    (net (code "17") (name "GEOMETRY_CV") (class "Default")
      (node (ref "C36") (pin "2") (pinfunction "2_2") (pintype "passive"))
      (node (ref "IC2") (pin "22") (pinfunction "PA6/SPI1_MISO/ADC6/TIM3_CH1_22") (pintype "bidirectional"))
      (node (ref "IC7") (pin "1") (pinfunction "VOUTA_1") (pintype "output"))
      (node (ref "R31") (pin "2") (pinfunction "2_2") (pintype "passive"))
    )
    (net (code "18") (name "GEOMETRY_POT") (class "Default")
      (node (ref "IC2") (pin "10") (pinfunction "PC2/SPI2_MISO/ADC12_10") (pintype "bidirectional"))
      (node (ref "R10") (pin "P$2") (pinfunction "2_P$2") (pintype "passive"))
    )
    (net (code "19") (name "GND") (class "Default")
      (node (ref "C1") (pin "+") (pinfunction "+_+") (pintype "passive"))
      (node (ref "C10") (pin "2") (pinfunction "2_2") (pintype "passive"))
      (node (ref "C11") (pin "2") (pinfunction "2_2") (pintype "passive"))
      (node (ref "C12") (pin "-") (pinfunction "-_-") (pintype "passive"))
      (node (ref "C13") (pin "2") (pinfunction "2_2") (pintype "passive"))
      (node (ref "C15") (pin "2") (pinfunction "2_2") (pintype "passive"))
      (node (ref "C16") (pin "2") (pinfunction "2_2") (pintype "passive"))
      (node (ref "C17") (pin "2") (pinfunction "2_2") (pintype "passive"))
      (node (ref "C18") (pin "2") (pinfunction "2_2") (pintype "passive"))
      (node (ref "C19") (pin "2") (pinfunction "2_2") (pintype "passive"))
      (node (ref "C2") (pin "-") (pinfunction "-_-") (pintype "passive"))
      (node (ref "C20") (pin "2") (pinfunction "2_2") (pintype "passive"))
      (node (ref "C21") (pin "-") (pinfunction "-_-") (pintype "passive"))
      (node (ref "C22") (pin "2") (pinfunction "2_2") (pintype "passive"))
      (node (ref "C25") (pin "2") (pinfunction "2_2") (pintype "passive"))
      (node (ref "C27") (pin "2") (pinfunction "2_2") (pintype "passive"))
      (node (ref "C3") (pin "-") (pinfunction "-_-") (pintype "passive"))
      (node (ref "C30") (pin "2") (pinfunction "2_2") (pintype "passive"))
      (node (ref "C31") (pin "2") (pinfunction "2_2") (pintype "passive"))
      (node (ref "C34") (pin "-") (pinfunction "-_-") (pintype "passive"))
      (node (ref "C35") (pin "2") (pinfunction "2_2") (pintype "passive"))
      (node (ref "C37") (pin "2") (pinfunction "2_2") (pintype "passive"))
      (node (ref "C39") (pin "2") (pinfunction "2_2") (pintype "passive"))
      (node (ref "C41") (pin "-") (pinfunction "-_-") (pintype "passive"))
      (node (ref "C44") (pin "2") (pinfunction "2_2") (pintype "passive"))
      (node (ref "C45") (pin "1") (pinfunction "1_1") (pintype "passive"))
      (node (ref "C46") (pin "-") (pinfunction "-_-") (pintype "passive"))
      (node (ref "C47") (pin "2") (pinfunction "2_2") (pintype "passive"))
      (node (ref "C48") (pin "2") (pinfunction "2_2") (pintype "passive"))
      (node (ref "C49") (pin "2") (pinfunction "2_2") (pintype "passive"))
      (node (ref "C6") (pin "2") (pinfunction "2_2") (pintype "passive"))
      (node (ref "C7") (pin "2") (pinfunction "2_2") (pintype "passive"))
      (node (ref "C8") (pin "-") (pinfunction "-_-") (pintype "passive"))
      (node (ref "C9") (pin "2") (pinfunction "2_2") (pintype "passive"))
      (node (ref "D3") (pin "1") (pinfunction "A_1") (pintype "passive"))
      (node (ref "IC1") (pin "1") (pinfunction "GND_1") (pintype "power_in"))
      (node (ref "IC2") (pin "12") (pinfunction "VSSA_12") (pintype "power_in"))
      (node (ref "IC2") (pin "18") (pinfunction "VSS_4_18") (pintype "power_in"))
      (node (ref "IC2") (pin "26") (pinfunction "PB0/ADC8/TIM3_CH3_26") (pintype "bidirectional"))
      (node (ref "IC2") (pin "28") (pinfunction "PB2/BOOT1_28") (pintype "bidirectional"))
      (node (ref "IC2") (pin "63") (pinfunction "VSS_3_63") (pintype "power_in"))
      (node (ref "IC3") (pin "1") (pinfunction "C_1") (pintype "passive"))
      (node (ref "IC4") (pin "6") (pinfunction "INH_6") (pintype "input"))
      (node (ref "IC4") (pin "7") (pinfunction "VEE_7") (pintype "power_in"))
      (node (ref "IC4") (pin "8") (pinfunction "GND_8") (pintype "power_in"))
      (node (ref "IC5") (pin "3") (pinfunction "+IN_3") (pintype "input"))
      (node (ref "IC5") (pin "4") (pinfunction "V-_4") (pintype "power_in"))
      (node (ref "IC5") (pin "5") (pinfunction "+IN_5") (pintype "input"))
      (node (ref "IC6") (pin "11") (pinfunction "HPGND_11") (pintype "bidirectional"))
      (node (ref "IC6") (pin "15") (pinfunction "AGND_15") (pintype "bidirectional"))
      (node (ref "IC6") (pin "21") (pinfunction "MODE_21") (pintype "bidirectional"))
      (node (ref "IC6") (pin "22") (pinfunction "CSB_22") (pintype "bidirectional"))
      (node (ref "IC6") (pin "28") (pinfunction "DGND_28") (pintype "bidirectional"))
      (node (ref "IC7") (pin "10") (pinfunction "VINC+_10") (pintype "input"))
      (node (ref "IC7") (pin "11") (pinfunction "VSS_11") (pintype "power_in"))
      (node (ref "IC7") (pin "12") (pinfunction "VIND+_12") (pintype "input"))
      (node (ref "IC7") (pin "3") (pinfunction "VINA+_3") (pintype "input"))
      (node (ref "IC7") (pin "5") (pinfunction "VINB+_5") (pintype "input"))
      (node (ref "IC8") (pin "3") (pinfunction "+IN_3") (pintype "input"))
      (node (ref "IC8") (pin "5") (pinfunction "+IN_5") (pintype "input"))
      (node (ref "J1") (pin "P$3") (pinfunction "1_P$3") (pintype "passive"))
      (node (ref "J10") (pin "P$3") (pinfunction "1_P$3") (pintype "passive"))
      (node (ref "J2") (pin "P$3") (pinfunction "1_P$3") (pintype "passive"))
      (node (ref "J3") (pin "P$3") (pinfunction "1_P$3") (pintype "passive"))
      (node (ref "J4") (pin "P$3") (pinfunction "1_P$3") (pintype "passive"))
      (node (ref "J5") (pin "P$3") (pinfunction "1_P$3") (pintype "passive"))
      (node (ref "J6") (pin "P$3") (pinfunction "1_P$3") (pintype "passive"))
      (node (ref "J7") (pin "P$3") (pinfunction "1_P$3") (pintype "passive"))
      (node (ref "J8") (pin "P$3") (pinfunction "1_P$3") (pintype "passive"))
      (node (ref "J9") (pin "P$3") (pinfunction "1_P$3") (pintype "passive"))
      (node (ref "JP1") (pin "3") (pinfunction "3_3") (pintype "passive"))
      (node (ref "JP1") (pin "5") (pinfunction "5_5") (pintype "passive"))
      (node (ref "JP1") (pin "9") (pinfunction "9_9") (pintype "passive"))
      (node (ref "JP3") (pin "3") (pinfunction "3_3") (pintype "passive"))
      (node (ref "JP3") (pin "4") (pinfunction "4_4") (pintype "passive"))
      (node (ref "JP3") (pin "5") (pinfunction "5_5") (pintype "passive"))
      (node (ref "JP3") (pin "6") (pinfunction "6_6") (pintype "passive"))
      (node (ref "JP3") (pin "7") (pinfunction "7_7") (pintype "passive"))
      (node (ref "JP3") (pin "8") (pinfunction "8_8") (pintype "passive"))
      (node (ref "LED1") (pin "2") (pinfunction "C_2") (pintype "bidirectional"))
      (node (ref "LED2") (pin "2") (pinfunction "C_2") (pintype "bidirectional"))
      (node (ref "Q1") (pin "GND") (pinfunction "GND_GND") (pintype "bidirectional"))
      (node (ref "Q2") (pin "E") (pinfunction "E_E") (pintype "passive"))
      (node (ref "Q3") (pin "GND") (pinfunction "GND_GND") (pintype "bidirectional"))
      (node (ref "R10") (pin "P$1") (pinfunction "1_P$1") (pintype "passive"))
      (node (ref "R27") (pin "1") (pinfunction "1_1") (pintype "passive"))
      (node (ref "R28") (pin "P$1") (pinfunction "1_P$1") (pintype "passive"))
      (node (ref "R29") (pin "P$1") (pinfunction "1_P$1") (pintype "passive"))
      (node (ref "R30") (pin "P$1") (pinfunction "1_P$1") (pintype "passive"))
      (node (ref "R33") (pin "1") (pinfunction "1_1") (pintype "passive"))
      (node (ref "R38") (pin "1") (pinfunction "1_1") (pintype "passive"))
      (node (ref "R45") (pin "P$1") (pinfunction "1_P$1") (pintype "passive"))
      (node (ref "R46") (pin "P$1") (pinfunction "1_P$1") (pintype "passive"))
      (node (ref "R47") (pin "P$1") (pinfunction "1_P$1") (pintype "passive"))
      (node (ref "R48") (pin "P$1") (pinfunction "1_P$1") (pintype "passive"))
      (node (ref "R49") (pin "P$1") (pinfunction "1_P$1") (pintype "passive"))
      (node (ref "R51") (pin "1") (pinfunction "1_1") (pintype "passive"))
      (node (ref "R61") (pin "1") (pinfunction "1_1") (pintype "passive"))
      (node (ref "R9") (pin "P$1") (pinfunction "1_P$1") (pintype "passive"))
      (node (ref "SW1") (pin "1") (pinfunction "1_1") (pintype "passive"))
      (node (ref "SW1") (pin "2") (pinfunction "2_2") (pintype "passive"))
      (node (ref "SW2") (pin "1") (pinfunction "1_1") (pintype "passive"))
      (node (ref "SW2") (pin "2") (pinfunction "2_2") (pintype "passive"))
    )
    (net (code "20") (name "I2C_SCL") (class "Default")
      (node (ref "IC2") (pin "29") (pinfunction "PB10/SPI2_SCK/I2S_SCK/I2C2_SCL/USART3_TX_29") (pintype "bidirectional"))
      (node (ref "IC6") (pin "24") (pinfunction "SCLK_24") (pintype "bidirectional"))
      (node (ref "R16") (pin "1") (pinfunction "1_1") (pintype "passive"))
    )
    (net (code "21") (name "I2C_SDA") (class "Default")
      (node (ref "IC2") (pin "30") (pinfunction "PB11/I2C2_SDA/USART3_RX_30") (pintype "bidirectional"))
      (node (ref "IC6") (pin "23") (pinfunction "SDIN_23") (pintype "bidirectional"))
      (node (ref "R17") (pin "1") (pinfunction "1_1") (pintype "passive"))
    )
    (net (code "22") (name "I2S_LRCK") (class "Default")
      (node (ref "IC2") (pin "33") (pinfunction "PB12/SPI2_NSS/I2S2_WS/I2C2_SMBA/USART3_CK/TIM1_BKIN_33") (pintype "bidirectional"))
      (node (ref "IC6") (pin "5") (pinfunction "DACLRC_5") (pintype "bidirectional"))
      (node (ref "IC6") (pin "7") (pinfunction "ADCLRC_7") (pintype "bidirectional"))
    )
    (net (code "23") (name "I2S_SCK") (class "Default")
      (node (ref "IC2") (pin "34") (pinfunction "PB13/SPI2_SCK/I2S2_SCK/USART3_CTS/TIM1_CH1N_34") (pintype "bidirectional"))
      (node (ref "IC6") (pin "3") (pinfunction "BCLK_3") (pintype "bidirectional"))
    )
    (net (code "24") (name "I2S_SIN") (class "Default")
      (node (ref "IC2") (pin "35") (pinfunction "PB14/SPI2_MISO/USART3_RTS/TIM1_CH2N_35") (pintype "bidirectional"))
      (node (ref "IC6") (pin "6") (pinfunction "ADCDAT_6") (pintype "bidirectional"))
    )
    (net (code "25") (name "I2S_SOUT") (class "Default")
      (node (ref "IC2") (pin "36") (pinfunction "PB15/SPI2_MOSI/I2S2_SD/TIM1_CH3N_36") (pintype "bidirectional"))
      (node (ref "IC6") (pin "4") (pinfunction "DACDAT_4") (pintype "bidirectional"))
    )
    (net (code "26") (name "IN_1") (class "Default")
      (node (ref "IC6") (pin "20") (pinfunction "LLINEIN_20") (pintype "bidirectional"))
      (node (ref "R27") (pin "2") (pinfunction "2_2") (pintype "passive"))
    )
    (net (code "27") (name "IN_2") (class "Default")
      (node (ref "C40") (pin "+") (pinfunction "+_+") (pintype "passive"))
      (node (ref "IC6") (pin "19") (pinfunction "RLINEIN_19") (pintype "bidirectional"))
    )
    (net (code "28") (name "JTCK") (class "Default")
      (node (ref "IC2") (pin "49") (pinfunction "PA14/JTCK-SWCLK_49") (pintype "bidirectional"))
      (node (ref "JP1") (pin "4") (pinfunction "4_4") (pintype "passive"))
    )
    (net (code "29") (name "JTDI") (class "Default")
      (node (ref "IC2") (pin "50") (pinfunction "PA15/JTDI/SPI3_NSS/I2S3_WS_50") (pintype "bidirectional"))
      (node (ref "JP1") (pin "8") (pinfunction "8_8") (pintype "passive"))
    )
    (net (code "30") (name "JTDO") (class "Default")
      (node (ref "IC2") (pin "55") (pinfunction "PB3/JTDO/SPI3_SCK/I2S3_SCK_55") (pintype "bidirectional"))
      (node (ref "JP1") (pin "6") (pinfunction "6_6") (pintype "passive"))
    )
    (net (code "31") (name "JTMS") (class "Default")
      (node (ref "IC2") (pin "46") (pinfunction "PA13/JTMS-SWDAT_46") (pintype "bidirectional"))
      (node (ref "JP1") (pin "2") (pinfunction "2_2") (pintype "passive"))
    )
    (net (code "32") (name "MAIN_OUT") (class "Default")
      (node (ref "C32") (pin "+") (pinfunction "+_+") (pintype "passive"))
      (node (ref "IC6") (pin "12") (pinfunction "LOUT_12") (pintype "bidirectional"))
    )
    (net (code "33") (name "MUXED_POTS") (class "Default")
      (node (ref "IC2") (pin "9") (pinfunction "PC1/ADC11_9") (pintype "bidirectional"))
      (node (ref "IC4") (pin "3") (pinfunction "X_3") (pintype "bidirectional"))
    )
    (net (code "34") (name "MUX_ADDR_0") (class "Default")
      (node (ref "IC2") (pin "59") (pinfunction "PB7/I2C1_SDA/TIM4_CH2/USART1_RX_59") (pintype "bidirectional"))
      (node (ref "IC4") (pin "11") (pinfunction "A_11") (pintype "input"))
    )
    (net (code "35") (name "MUX_ADDR_1") (class "Default")
      (node (ref "IC2") (pin "58") (pinfunction "PB6/I2C1_SCL/TIM4_CH1/USART1_TX_58") (pintype "bidirectional"))
      (node (ref "IC4") (pin "10") (pinfunction "B_10") (pintype "input"))
    )
    (net (code "36") (name "MUX_ADDR_2") (class "Default")
      (node (ref "IC2") (pin "57") (pinfunction "PB5/I2C1_SMBA/SPI1_MOSI/SPI3_MOSI/I2S3_SD_57") (pintype "bidirectional"))
      (node (ref "IC4") (pin "9") (pinfunction "C_9") (pintype "input"))
    )
    (net (code "37") (name "NORMALIZATION_PROBE") (class "Default")
      (node (ref "D3") (pin "3") (pinfunction "AC_3") (pintype "passive"))
      (node (ref "IC2") (pin "39") (pinfunction "PC8_39") (pintype "bidirectional"))
      (node (ref "R52") (pin "1") (pinfunction "1_1") (pintype "passive"))
      (node (ref "R53") (pin "1") (pinfunction "1_1") (pintype "passive"))
      (node (ref "R57") (pin "1") (pinfunction "1_1") (pintype "passive"))
    )
    (net (code "38") (name "Net-(C32-Pad-)") (class "Default")
      (node (ref "C32") (pin "-") (pinfunction "-_-") (pintype "passive"))
      (node (ref "R33") (pin "2") (pinfunction "2_2") (pintype "passive"))
      (node (ref "R40") (pin "1") (pinfunction "1_1") (pintype "passive"))
    )
    (net (code "39") (name "Net-(C33-Pad-)") (class "Default")
      (node (ref "C33") (pin "-") (pinfunction "-_-") (pintype "passive"))
      (node (ref "R38") (pin "2") (pinfunction "2_2") (pintype "passive"))
      (node (ref "R43") (pin "1") (pinfunction "1_1") (pintype "passive"))
    )
    (net (code "40") (name "Net-(C40-Pad-)") (class "Default")
      (node (ref "C40") (pin "-") (pinfunction "-_-") (pintype "passive"))
      (node (ref "C49") (pin "1") (pinfunction "1_1") (pintype "passive"))
      (node (ref "R51") (pin "2") (pinfunction "2_2") (pintype "passive"))
      (node (ref "R54") (pin "2") (pinfunction "2_2") (pintype "passive"))
    )
    (net (code "41") (name "Net-(D1-PadA)") (class "Default")
      (node (ref "D1") (pin "A") (pinfunction "A_A") (pintype "passive"))
      (node (ref "L1") (pin "1") (pinfunction "1_1") (pintype "passive"))
    )
    (net (code "42") (name "Net-(D2-PadC)") (class "Default")
      (node (ref "D2") (pin "C") (pinfunction "C_C") (pintype "passive"))
      (node (ref "L2") (pin "1") (pinfunction "1_1") (pintype "passive"))
    )
    (net (code "43") (name "Net-(IC1-VIN)") (class "Default")
      (node (ref "C2") (pin "+") (pinfunction "+_+") (pintype "passive"))
      (node (ref "IC1") (pin "2") (pinfunction "VIN_2") (pintype "input"))
      (node (ref "R2") (pin "1") (pinfunction "1_1") (pintype "passive"))
    )
    (net (code "44") (name "Net-(IC2-PC0{slash}ADC10)") (class "Default")
      (node (ref "IC2") (pin "8") (pinfunction "PC0/ADC10_8") (pintype "bidirectional"))
      (node (ref "R4") (pin "1") (pinfunction "1_1") (pintype "passive"))
    )
    (net (code "45") (name "Net-(IC2-PC10{slash}SPI3_SCK{slash}I2S3_SCK{slash}UART4_TX)") (class "Default")
      (node (ref "IC2") (pin "51") (pinfunction "PC10/SPI3_SCK/I2S3_SCK/UART4_TX_51") (pintype "bidirectional"))
      (node (ref "R5") (pin "1") (pinfunction "1_1") (pintype "passive"))
    )
    (net (code "46") (name "Net-(IC2-PC11{slash}UART4_RX{slash}SPI3_MISO{slash}USART3_RX)") (class "Default")
      (node (ref "IC2") (pin "52") (pinfunction "PC11/UART4_RX/SPI3_MISO/USART3_RX_52") (pintype "bidirectional"))
      (node (ref "R3") (pin "1") (pinfunction "1_1") (pintype "passive"))
    )
    (net (code "47") (name "Net-(IC2-PC12{slash}UART5_TX{slash}I2S3_SD{slash}USART3_CK)") (class "Default")
      (node (ref "IC2") (pin "53") (pinfunction "PC12/UART5_TX/I2S3_SD/USART3_CK_53") (pintype "bidirectional"))
      (node (ref "R1") (pin "1") (pinfunction "1_1") (pintype "passive"))
    )
    (net (code "48") (name "Net-(IC2-PD0{slash}OSC_IN)") (class "Default")
      (node (ref "IC2") (pin "5") (pinfunction "PD0/OSC_IN_5") (pintype "bidirectional"))
      (node (ref "Q1") (pin "X2") (pinfunction "X2_X2") (pintype "bidirectional"))
    )
    (net (code "49") (name "Net-(IC2-PD1{slash}OSC_OUT)") (class "Default")
      (node (ref "IC2") (pin "6") (pinfunction "PD1/OSC_OUT_6") (pintype "bidirectional"))
      (node (ref "Q1") (pin "X1") (pinfunction "X1_X1") (pintype "bidirectional"))
    )
    (net (code "50") (name "Net-(IC2-VCAP_1)") (class "Default")
      (node (ref "C16") (pin "1") (pinfunction "1_1") (pintype "passive"))
      (node (ref "IC2") (pin "31") (pinfunction "VCAP_1_31") (pintype "power_in"))
    )
    (net (code "51") (name "Net-(IC2-VCAP_2)") (class "Default")
      (node (ref "C22") (pin "1") (pinfunction "1_1") (pintype "passive"))
      (node (ref "IC2") (pin "47") (pinfunction "VCAP_2_47") (pintype "power_in"))
    )
    (net (code "52") (name "Net-(IC5A--IN)") (class "Default")
      (node (ref "C26") (pin "1") (pinfunction "1_1") (pintype "passive"))
      (node (ref "IC5") (pin "2") (pinfunction "-IN_2") (pintype "input"))
      (node (ref "R18") (pin "1") (pinfunction "1_1") (pintype "passive"))
      (node (ref "R19") (pin "2") (pinfunction "2_2") (pintype "passive"))
      (node (ref "R20") (pin "2") (pinfunction "2_2") (pintype "passive"))
    )
    (net (code "53") (name "Net-(IC5B--IN)") (class "Default")
      (node (ref "C14") (pin "1") (pinfunction "1_1") (pintype "passive"))
      (node (ref "IC5") (pin "6") (pinfunction "-IN_6") (pintype "input"))
      (node (ref "R13") (pin "1") (pinfunction "1_1") (pintype "passive"))
      (node (ref "R14") (pin "2") (pinfunction "2_2") (pintype "passive"))
      (node (ref "R15") (pin "2") (pinfunction "2_2") (pintype "passive"))
    )
    (net (code "54") (name "Net-(IC6-VMID)") (class "Default")
      (node (ref "C34") (pin "+") (pinfunction "+_+") (pintype "passive"))
      (node (ref "C35") (pin "1") (pinfunction "1_1") (pintype "passive"))
      (node (ref "IC6") (pin "16") (pinfunction "VMID_16") (pintype "bidirectional"))
    )
    (net (code "55") (name "Net-(IC6-XTI{slash}MCLK)") (class "Default")
      (node (ref "IC6") (pin "25") (pinfunction "XTI/MCLK_25") (pintype "bidirectional"))
      (node (ref "Q3") (pin "X1") (pinfunction "X1_X1") (pintype "bidirectional"))
    )
    (net (code "56") (name "Net-(IC6-XTO)") (class "Default")
      (node (ref "IC6") (pin "26") (pinfunction "XTO_26") (pintype "bidirectional"))
      (node (ref "Q3") (pin "X2") (pinfunction "X2_X2") (pintype "bidirectional"))
    )
    (net (code "57") (name "Net-(IC7-VINA-)") (class "Default")
      (node (ref "C36") (pin "1") (pinfunction "1_1") (pintype "passive"))
      (node (ref "IC7") (pin "2") (pinfunction "VINA-_2") (pintype "input"))
      (node (ref "R31") (pin "1") (pinfunction "1_1") (pintype "passive"))
      (node (ref "R34") (pin "2") (pinfunction "2_2") (pintype "passive"))
      (node (ref "R36") (pin "2") (pinfunction "2_2") (pintype "passive"))
    )
    (net (code "58") (name "Net-(IC7-VINB-)") (class "Default")
      (node (ref "C38") (pin "1") (pinfunction "1_1") (pintype "passive"))
      (node (ref "IC7") (pin "6") (pinfunction "VINB-_6") (pintype "input"))
      (node (ref "R32") (pin "1") (pinfunction "1_1") (pintype "passive"))
      (node (ref "R35") (pin "2") (pinfunction "2_2") (pintype "passive"))
      (node (ref "R37") (pin "2") (pinfunction "2_2") (pintype "passive"))
    )
    (net (code "59") (name "Net-(IC7-VINC-)") (class "Default")
      (node (ref "C29") (pin "2") (pinfunction "2_2") (pintype "passive"))
      (node (ref "IC7") (pin "9") (pinfunction "VINC-_9") (pintype "input"))
      (node (ref "R22") (pin "1") (pinfunction "1_1") (pintype "passive"))
      (node (ref "R24") (pin "1") (pinfunction "1_1") (pintype "passive"))
      (node (ref "R26") (pin "2") (pinfunction "2_2") (pintype "passive"))
    )
    (net (code "60") (name "Net-(IC7-VIND-)") (class "Default")
      (node (ref "C28") (pin "2") (pinfunction "2_2") (pintype "passive"))
      (node (ref "IC7") (pin "13") (pinfunction "VIND-_13") (pintype "input"))
      (node (ref "R21") (pin "1") (pinfunction "1_1") (pintype "passive"))
      (node (ref "R23") (pin "1") (pinfunction "1_1") (pintype "passive"))
      (node (ref "R25") (pin "2") (pinfunction "2_2") (pintype "passive"))
    )
    (net (code "61") (name "Net-(IC8A--IN)") (class "Default")
      (node (ref "C42") (pin "1") (pinfunction "1_1") (pintype "passive"))
      (node (ref "IC8") (pin "2") (pinfunction "-IN_2") (pintype "input"))
      (node (ref "R39") (pin "2") (pinfunction "2_2") (pintype "passive"))
      (node (ref "R40") (pin "2") (pinfunction "2_2") (pintype "passive"))
      (node (ref "R41") (pin "1") (pinfunction "1_1") (pintype "passive"))
    )
    (net (code "62") (name "Net-(IC8A-OUT)") (class "Default")
      (node (ref "C42") (pin "2") (pinfunction "2_2") (pintype "passive"))
      (node (ref "IC8") (pin "1") (pinfunction "OUT_1") (pintype "output"))
      (node (ref "R41") (pin "2") (pinfunction "2_2") (pintype "passive"))
      (node (ref "R55") (pin "1") (pinfunction "1_1") (pintype "passive"))
    )
    (net (code "63") (name "Net-(IC8B--IN)") (class "Default")
      (node (ref "C43") (pin "1") (pinfunction "1_1") (pintype "passive"))
      (node (ref "IC8") (pin "6") (pinfunction "-IN_6") (pintype "input"))
      (node (ref "R42") (pin "1") (pinfunction "1_1") (pintype "passive"))
      (node (ref "R43") (pin "2") (pinfunction "2_2") (pintype "passive"))
      (node (ref "R44") (pin "2") (pinfunction "2_2") (pintype "passive"))
    )
    (net (code "64") (name "Net-(IC8B-OUT)") (class "Default")
      (node (ref "C43") (pin "2") (pinfunction "2_2") (pintype "passive"))
      (node (ref "IC8") (pin "7") (pinfunction "OUT_7") (pintype "output"))
      (node (ref "R42") (pin "2") (pinfunction "2_2") (pintype "passive"))
      (node (ref "R56") (pin "1") (pinfunction "1_1") (pintype "passive"))
    )
    (net (code "65") (name "Net-(J1-2)") (class "Default")
      (node (ref "J1") (pin "P$1") (pinfunction "2_P$1") (pintype "passive"))
      (node (ref "R19") (pin "1") (pinfunction "1_1") (pintype "passive"))
    )
    (net (code "66") (name "Net-(J2-2)") (class "Default")
      (node (ref "J2") (pin "P$1") (pinfunction "2_P$1") (pintype "passive"))
      (node (ref "R22") (pin "2") (pinfunction "2_2") (pintype "passive"))
    )
    (net (code "67") (name "Net-(J2-3)") (class "Default")
      (node (ref "J2") (pin "P$2") (pinfunction "3_P$2") (pintype "passive"))
      (node (ref "R50") (pin "2") (pinfunction "2_2") (pintype "passive"))
    )
    (net (code "68") (name "Net-(J3-2)") (class "Default")
      (node (ref "J3") (pin "P$1") (pinfunction "2_P$1") (pintype "passive"))
      (node (ref "R21") (pin "2") (pinfunction "2_2") (pintype "passive"))
    )
    (net (code "69") (name "Net-(J4-2)") (class "Default")
      (node (ref "J4") (pin "P$1") (pinfunction "2_P$1") (pintype "passive"))
      (node (ref "R34") (pin "1") (pinfunction "1_1") (pintype "passive"))
    )
    (net (code "70") (name "Net-(J5-2)") (class "Default")
      (node (ref "J5") (pin "P$1") (pinfunction "2_P$1") (pintype "passive"))
      (node (ref "R35") (pin "1") (pinfunction "1_1") (pintype "passive"))
    )
    (net (code "71") (name "Net-(J6-2)") (class "Default")
      (node (ref "J6") (pin "P$1") (pinfunction "2_P$1") (pintype "passive"))
      (node (ref "R11") (pin "1") (pinfunction "1_1") (pintype "passive"))
    )
    (net (code "72") (name "Net-(J6-3)") (class "Default")
      (node (ref "J6") (pin "P$2") (pinfunction "3_P$2") (pintype "passive"))
      (node (ref "R52") (pin "2") (pinfunction "2_2") (pintype "passive"))
    )
    (net (code "73") (name "Net-(J7-2)") (class "Default")
      (node (ref "J7") (pin "P$1") (pinfunction "2_P$1") (pintype "passive"))
      (node (ref "R14") (pin "1") (pinfunction "1_1") (pintype "passive"))
    )
    (net (code "74") (name "Net-(J8-2)") (class "Default")
      (node (ref "J8") (pin "P$1") (pinfunction "2_P$1") (pintype "passive"))
      (node (ref "R54") (pin "1") (pinfunction "1_1") (pintype "passive"))
    )
    (net (code "75") (name "Net-(J8-3)") (class "Default")
      (node (ref "J8") (pin "P$2") (pinfunction "3_P$2") (pintype "passive"))
      (node (ref "R53") (pin "2") (pinfunction "2_2") (pintype "passive"))
    )
    (net (code "76") (name "Net-(J9-2)") (class "Default")
      (node (ref "J9") (pin "P$1") (pinfunction "2_P$1") (pintype "passive"))
      (node (ref "R55") (pin "2") (pinfunction "2_2") (pintype "passive"))
    )
    (net (code "77") (name "Net-(J9-3)") (class "Default")
      (node (ref "J9") (pin "P$2") (pinfunction "3_P$2") (pintype "passive"))
      (node (ref "SJ1") (pin "2") (pinfunction "2_2") (pintype "passive"))
    )
    (net (code "78") (name "Net-(J10-2)") (class "Default")
      (node (ref "J10") (pin "P$1") (pinfunction "2_P$1") (pintype "passive"))
      (node (ref "R56") (pin "2") (pinfunction "2_2") (pintype "passive"))
    )
    (net (code "79") (name "Net-(J10-3)") (class "Default")
      (node (ref "J10") (pin "P$2") (pinfunction "3_P$2") (pintype "passive"))
      (node (ref "R39") (pin "1") (pinfunction "1_1") (pintype "passive"))
    )
    (net (code "80") (name "Net-(JP3-Pad1)") (class "Default")
      (node (ref "JP3") (pin "1") (pinfunction "1_1") (pintype "passive"))
      (node (ref "JP3") (pin "2") (pinfunction "2_2") (pintype "passive"))
      (node (ref "L1") (pin "2") (pinfunction "2_2") (pintype "passive"))
    )
    (net (code "81") (name "Net-(JP3-Pad10)") (class "Default")
      (node (ref "JP3") (pin "10") (pinfunction "10_10") (pintype "passive"))
      (node (ref "JP3") (pin "9") (pinfunction "9_9") (pintype "passive"))
      (node (ref "L2") (pin "2") (pinfunction "2_2") (pintype "passive"))
    )
    (net (code "82") (name "Net-(LED1-GRN)") (class "Default")
      (node (ref "LED1") (pin "1") (pinfunction "GRN_1") (pintype "bidirectional"))
      (node (ref "R3") (pin "2") (pinfunction "2_2") (pintype "passive"))
    )
    (net (code "83") (name "Net-(LED1-RED)") (class "Default")
      (node (ref "LED1") (pin "3") (pinfunction "RED_3") (pintype "bidirectional"))
      (node (ref "R1") (pin "2") (pinfunction "2_2") (pintype "passive"))
    )
    (net (code "84") (name "Net-(LED2-GRN)") (class "Default")
      (node (ref "LED2") (pin "1") (pinfunction "GRN_1") (pintype "bidirectional"))
      (node (ref "R5") (pin "2") (pinfunction "2_2") (pintype "passive"))
    )
    (net (code "85") (name "Net-(LED2-RED)") (class "Default")
      (node (ref "LED2") (pin "3") (pinfunction "RED_3") (pintype "bidirectional"))
      (node (ref "R4") (pin "2") (pinfunction "2_2") (pintype "passive"))
    )
    (net (code "86") (name "Net-(Q2-PadB)") (class "Default")
      (node (ref "Q2") (pin "B") (pinfunction "B_B") (pintype "passive"))
      (node (ref "R11") (pin "2") (pinfunction "2_2") (pintype "passive"))
    )
    (net (code "87") (name "Net-(R44-Pad1)") (class "Default")
      (node (ref "R44") (pin "1") (pinfunction "1_1") (pintype "passive"))
      (node (ref "SJ1") (pin "1") (pinfunction "1_1") (pintype "passive"))
    )
    (net (code "88") (name "POSITION_ATT") (class "Default")
      (node (ref "IC4") (pin "15") (pinfunction "X2_15") (pintype "bidirectional"))
      (node (ref "R49") (pin "P$2") (pinfunction "2_P$2") (pintype "passive"))
    )
    (net (code "89") (name "POSITION_CV") (class "Default")
      (node (ref "C38") (pin "2") (pinfunction "2_2") (pintype "passive"))
      (node (ref "IC2") (pin "23") (pinfunction "PA7/SPI1_MOSI/ADC7/TIM3_CH2_23") (pintype "bidirectional"))
      (node (ref "IC7") (pin "7") (pinfunction "VOUTB_7") (pintype "output"))
      (node (ref "R32") (pin "2") (pinfunction "2_2") (pintype "passive"))
    )
    (net (code "90") (name "POSITION_POT") (class "Default")
      (node (ref "IC4") (pin "12") (pinfunction "X3_12") (pintype "bidirectional"))
      (node (ref "R30") (pin "P$2") (pinfunction "2_P$2") (pintype "passive"))
    )
    (net (code "91") (name "RESET") (class "Default")
      (node (ref "IC2") (pin "7") (pinfunction "NRST_7") (pintype "bidirectional"))
      (node (ref "JP1") (pin "10") (pinfunction "10_10") (pintype "passive"))
      (node (ref "R60") (pin "1") (pinfunction "1_1") (pintype "passive"))
    )
    (net (code "92") (name "RX") (class "Default")
      (node (ref "IC2") (pin "43") (pinfunction "PA10/USART1_RX/TIM1_CH3_43") (pintype "bidirectional"))
    )
    (net (code "93") (name "STRUM") (class "Default")
      (node (ref "IC2") (pin "16") (pinfunction "PA2/USART2_TX/ADC2/TIM2_CH3_16") (pintype "bidirectional"))
      (node (ref "Q2") (pin "C") (pinfunction "C_C") (pintype "passive"))
      (node (ref "R8") (pin "1") (pinfunction "1_1") (pintype "passive"))
    )
    (net (code "94") (name "SW_MODE") (class "Default")
      (node (ref "IC2") (pin "61") (pinfunction "PB8/TIM4_CH3/I2C1_SCL_61") (pintype "bidirectional"))
      (node (ref "SW2") (pin "3") (pinfunction "3_3") (pintype "passive"))
      (node (ref "SW2") (pin "4") (pinfunction "4_4") (pintype "passive"))
    )
    (net (code "95") (name "SW_POLYPHONY") (class "Default")
      (node (ref "IC2") (pin "62") (pinfunction "PB9/SPI2_NSS/I2S2_WS/I2C1_SDA/TIM4_CH4_62") (pintype "bidirectional"))
      (node (ref "SW1") (pin "3") (pinfunction "3_3") (pintype "passive"))
      (node (ref "SW1") (pin "4") (pinfunction "4_4") (pintype "passive"))
    )
    (net (code "96") (name "TX") (class "Default")
      (node (ref "IC2") (pin "42") (pinfunction "PA9/USART1_TX/TIM1_CH2_42") (pintype "bidirectional"))
    )
    (net (code "97") (name "VBAT") (class "Default")
      (node (ref "IC2") (pin "1") (pinfunction "VBAT_1") (pintype "power_in"))
    )
    (net (code "98") (name "VCC") (class "Default")
      (node (ref "C3") (pin "+") (pinfunction "+_+") (pintype "passive"))
      (node (ref "C39") (pin "1") (pinfunction "1_1") (pintype "passive"))
      (node (ref "D1") (pin "C") (pinfunction "C_C") (pintype "passive"))
      (node (ref "IC8") (pin "8") (pinfunction "V+_8") (pintype "power_in"))
      (node (ref "R2") (pin "2") (pinfunction "2_2") (pintype "passive"))
    )
    (net (code "99") (name "VEE") (class "Default")
      (node (ref "C1") (pin "-") (pinfunction "-_-") (pintype "passive"))
      (node (ref "C45") (pin "2") (pinfunction "2_2") (pintype "passive"))
      (node (ref "D2") (pin "A") (pinfunction "A_A") (pintype "passive"))
      (node (ref "IC8") (pin "4") (pinfunction "V-_4") (pintype "power_in"))
      (node (ref "R12") (pin "2") (pinfunction "2_2") (pintype "passive"))
    )
    (net (code "100") (name "V_OCT_CV") (class "Default")
      (node (ref "C14") (pin "2") (pinfunction "2_2") (pintype "passive"))
      (node (ref "IC2") (pin "15") (pinfunction "PA1/USART2_RTS/UART4_RX/ADC1/TIM2_CH2_15") (pintype "bidirectional"))
      (node (ref "IC5") (pin "7") (pinfunction "OUT_7") (pintype "output"))
      (node (ref "R13") (pin "2") (pinfunction "2_2") (pintype "passive"))
    )
    (net (code "101") (name "unconnected-(IC2-PA3{slash}USART2_RX{slash}ADC3{slash}TIM2_CH4-Pad17)") (class "Default")
      (node (ref "IC2") (pin "17") (pinfunction "PA3/USART2_RX/ADC3/TIM2_CH4_17") (pintype "bidirectional"))
    )
    (net (code "102") (name "unconnected-(IC2-PA8{slash}USART1_CK{slash}TIM1_CH1{slash}MCO-Pad41)") (class "Default")
      (node (ref "IC2") (pin "41") (pinfunction "PA8/USART1_CK/TIM1_CH1/MCO_41") (pintype "bidirectional"))
    )
    (net (code "103") (name "unconnected-(IC2-PA11{slash}USART1_CTS{slash}CANRX{slash}USBDM{slash}TIM1_CH4-Pad44)") (class "Default")
      (node (ref "IC2") (pin "44") (pinfunction "PA11/USART1_CTS/CANRX/USBDM/TIM1_CH4_44") (pintype "bidirectional"))
    )
    (net (code "104") (name "unconnected-(IC2-PA12{slash}USART1_RTS{slash}CANTX{slash}USBDP{slash}TIM1_ETR-Pad45)") (class "Default")
      (node (ref "IC2") (pin "45") (pinfunction "PA12/USART1_RTS/CANTX/USBDP/TIM1_ETR_45") (pintype "bidirectional"))
    )
    (net (code "105") (name "unconnected-(IC2-PB1{slash}ADC9{slash}TIM3_CH4-Pad27)") (class "Default")
      (node (ref "IC2") (pin "27") (pinfunction "PB1/ADC9/TIM3_CH4_27") (pintype "bidirectional"))
    )
    (net (code "106") (name "unconnected-(IC2-PB4{slash}NJTRST{slash}SPI3_MISO{slash}SPI1_MISO-Pad56)") (class "Default")
      (node (ref "IC2") (pin "56") (pinfunction "PB4/NJTRST/SPI3_MISO/SPI1_MISO_56") (pintype "bidirectional"))
    )
    (net (code "107") (name "unconnected-(IC2-PC4{slash}ADC14-Pad24)") (class "Default")
      (node (ref "IC2") (pin "24") (pinfunction "PC4/ADC14_24") (pintype "bidirectional"))
    )
    (net (code "108") (name "unconnected-(IC2-PC5{slash}ADC15-Pad25)") (class "Default")
      (node (ref "IC2") (pin "25") (pinfunction "PC5/ADC15_25") (pintype "bidirectional"))
    )
    (net (code "109") (name "unconnected-(IC2-PC6{slash}I2S2_MCK-Pad37)") (class "Default")
      (node (ref "IC2") (pin "37") (pinfunction "PC6/I2S2_MCK_37") (pintype "bidirectional"))
    )
    (net (code "110") (name "unconnected-(IC2-PC7{slash}I2S3_MCK-Pad38)") (class "Default")
      (node (ref "IC2") (pin "38") (pinfunction "PC7/I2S3_MCK_38") (pintype "bidirectional"))
    )
    (net (code "111") (name "unconnected-(IC2-PC9{slash}I2S2_CKIN{slash}I2S3_CKIN-Pad40)") (class "Default")
      (node (ref "IC2") (pin "40") (pinfunction "PC9/I2S2_CKIN/I2S3_CKIN_40") (pintype "bidirectional"))
    )
    (net (code "112") (name "unconnected-(IC2-PC13-TAMPER-RTC-Pad2)") (class "Default")
      (node (ref "IC2") (pin "2") (pinfunction "PC13-TAMPER-RTC_2") (pintype "bidirectional"))
    )
    (net (code "113") (name "unconnected-(IC2-PC14{slash}OSC32_IN-Pad3)") (class "Default")
      (node (ref "IC2") (pin "3") (pinfunction "PC14/OSC32_IN_3") (pintype "bidirectional"))
    )
    (net (code "114") (name "unconnected-(IC2-PC15{slash}OSC_OUT-Pad4)") (class "Default")
      (node (ref "IC2") (pin "4") (pinfunction "PC15/OSC_OUT_4") (pintype "bidirectional"))
    )
    (net (code "115") (name "unconnected-(IC2-PD2{slash}TIM3-ETR-Pad54)") (class "Default")
      (node (ref "IC2") (pin "54") (pinfunction "PD2/TIM3-ETR_54") (pintype "bidirectional"))
    )
    (net (code "116") (name "unconnected-(IC6-CLKOUT-Pad2)") (class "Default")
      (node (ref "IC6") (pin "2") (pinfunction "CLKOUT_2") (pintype "bidirectional"))
    )
    (net (code "117") (name "unconnected-(IC6-LHPOUT-Pad9)") (class "Default")
      (node (ref "IC6") (pin "9") (pinfunction "LHPOUT_9") (pintype "bidirectional"))
    )
    (net (code "118") (name "unconnected-(IC6-MICBIAS-Pad17)") (class "Default")
      (node (ref "IC6") (pin "17") (pinfunction "MICBIAS_17") (pintype "bidirectional"))
    )
    (net (code "119") (name "unconnected-(IC6-MICIN-Pad18)") (class "Default")
      (node (ref "IC6") (pin "18") (pinfunction "MICIN_18") (pintype "bidirectional"))
    )
    (net (code "120") (name "unconnected-(IC6-RHPOUT-Pad10)") (class "Default")
      (node (ref "IC6") (pin "10") (pinfunction "RHPOUT_10") (pintype "bidirectional"))
    )
    (net (code "121") (name "unconnected-(J1-3-PadP$2)") (class "Default")
      (node (ref "J1") (pin "P$2") (pinfunction "3_P$2") (pintype "passive"))
    )
    (net (code "122") (name "unconnected-(J3-3-PadP$2)") (class "Default")
      (node (ref "J3") (pin "P$2") (pinfunction "3_P$2") (pintype "passive"))
    )
    (net (code "123") (name "unconnected-(J4-3-PadP$2)") (class "Default")
      (node (ref "J4") (pin "P$2") (pinfunction "3_P$2") (pintype "passive"))
    )
    (net (code "124") (name "unconnected-(J5-3-PadP$2)") (class "Default")
      (node (ref "J5") (pin "P$2") (pinfunction "3_P$2") (pintype "passive"))
    )
    (net (code "125") (name "unconnected-(JP1-Pad7)") (class "Default")
      (node (ref "JP1") (pin "7") (pinfunction "7_7") (pintype "passive"))
    )
  )
)
